# octanis_eps_v1.net
KiCad netlist of a schematic drawn in EAGLE
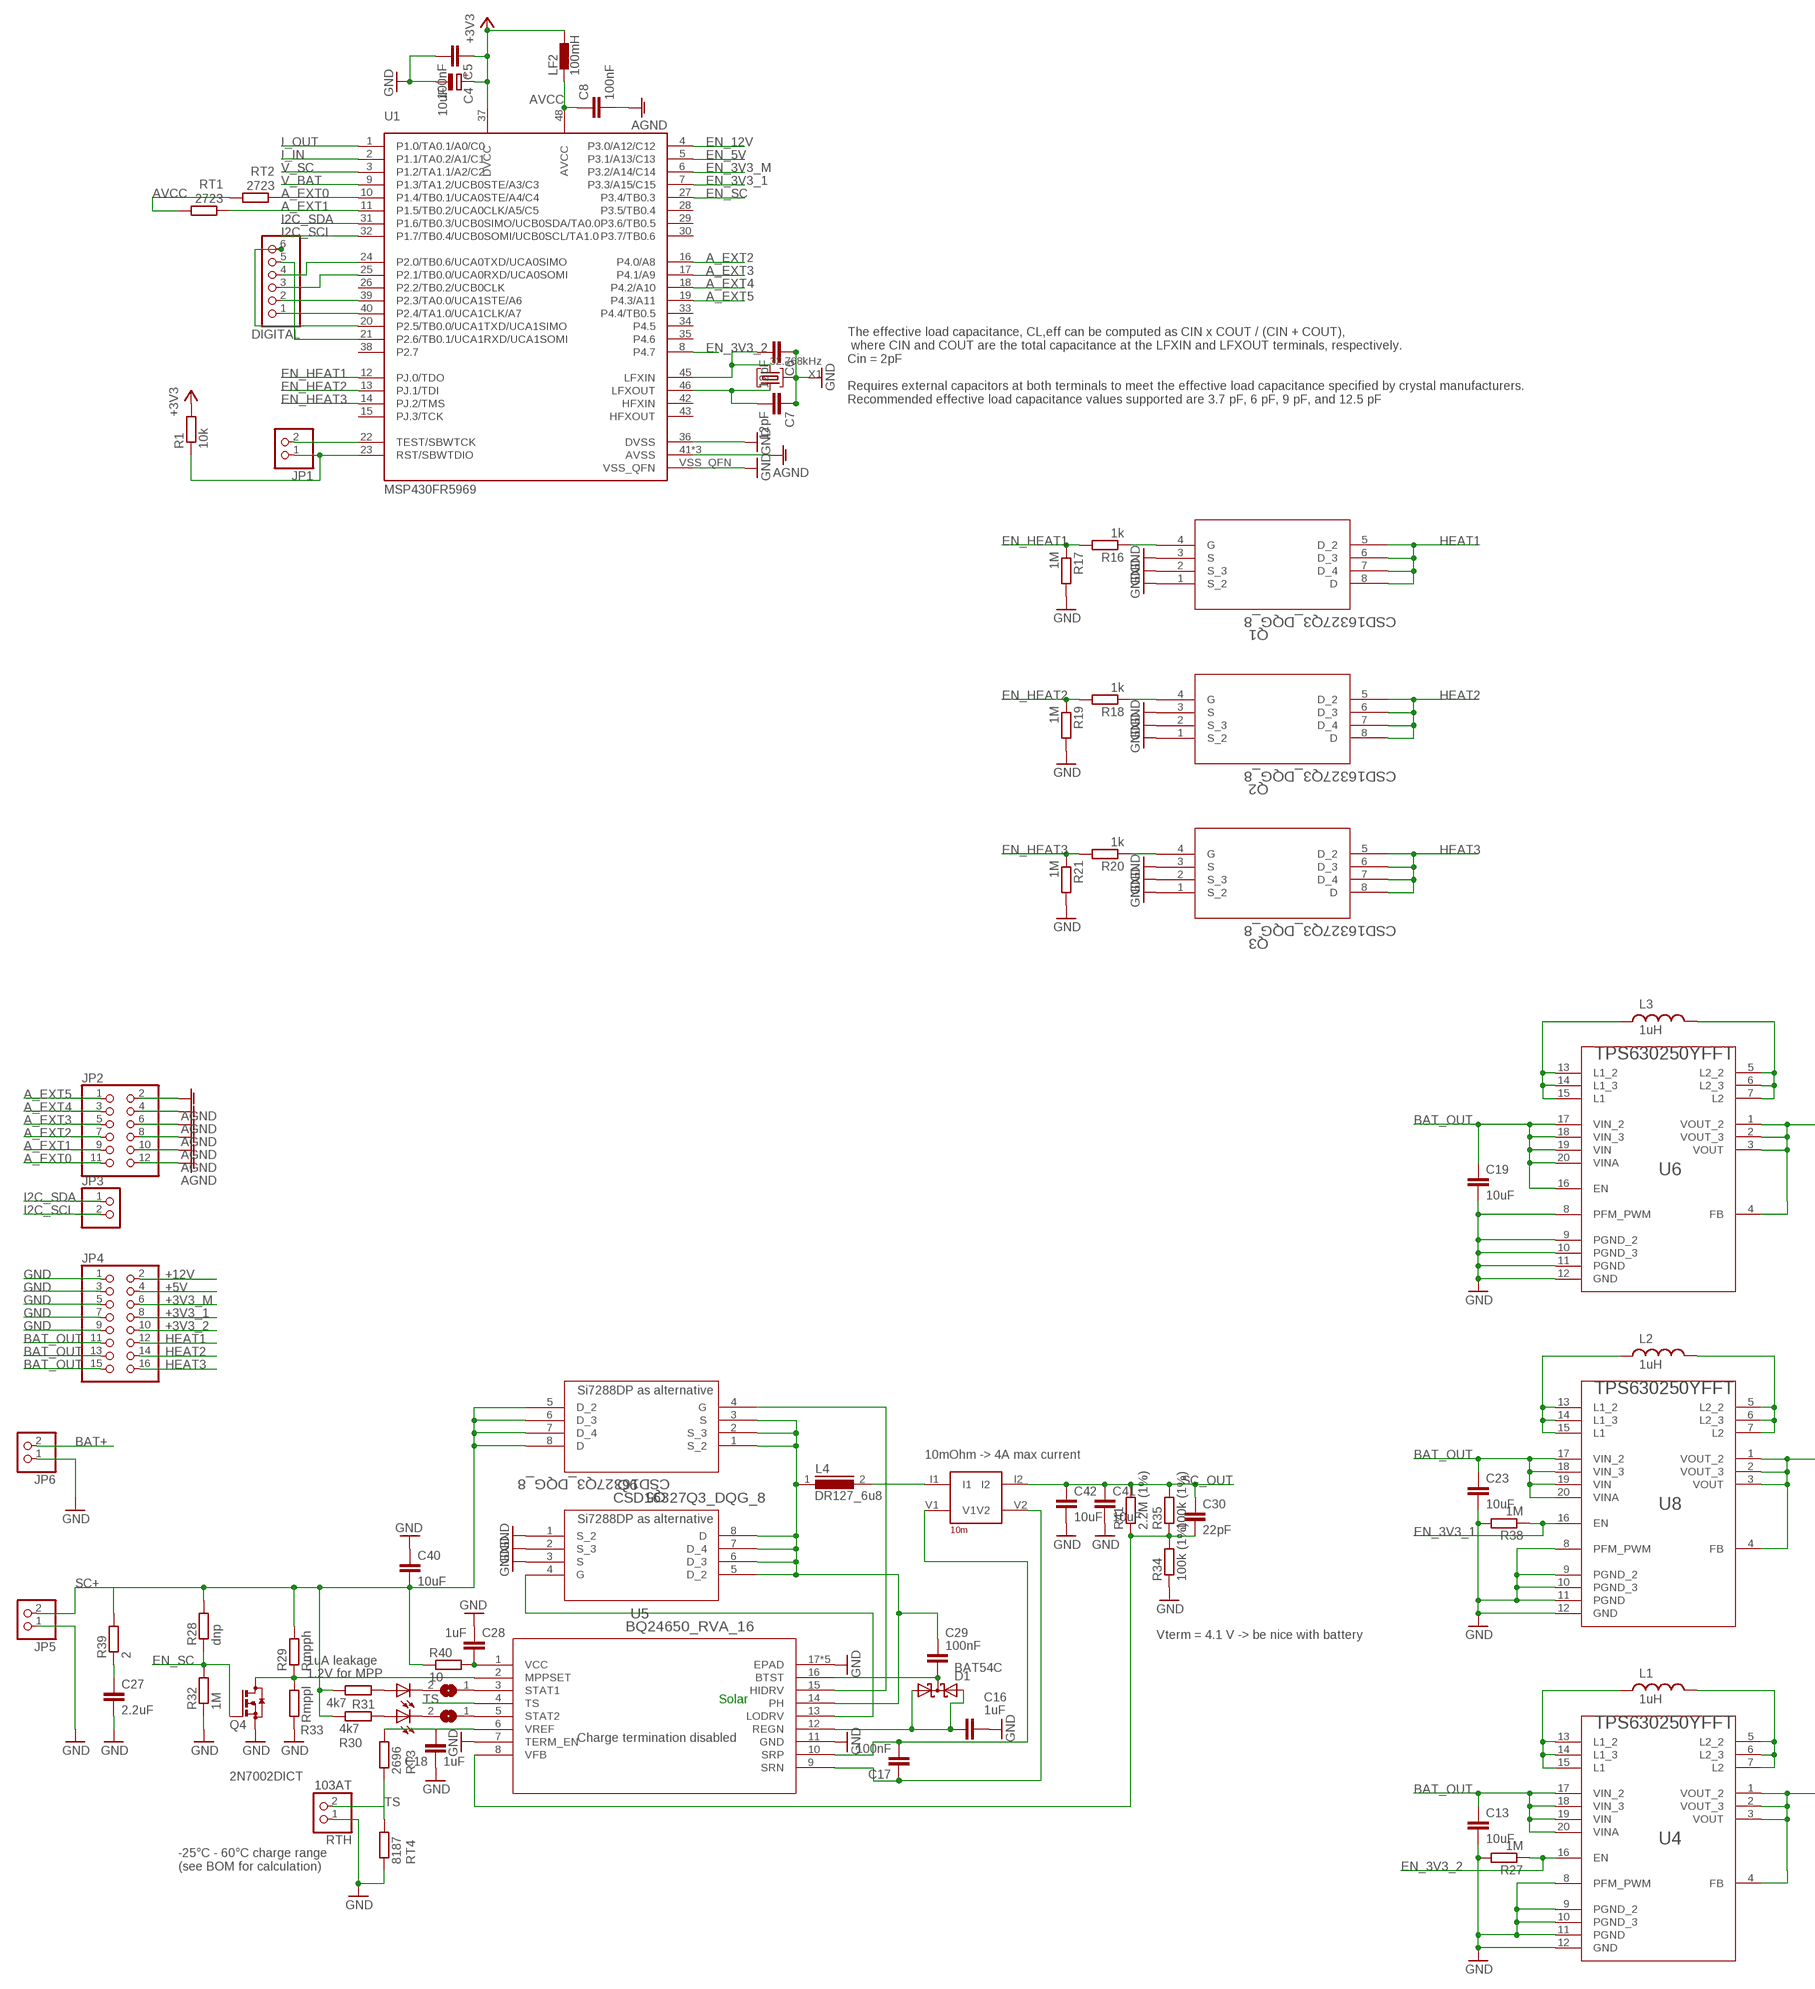
[diagram p0: schematic, sheet 1, part 1 of 2]
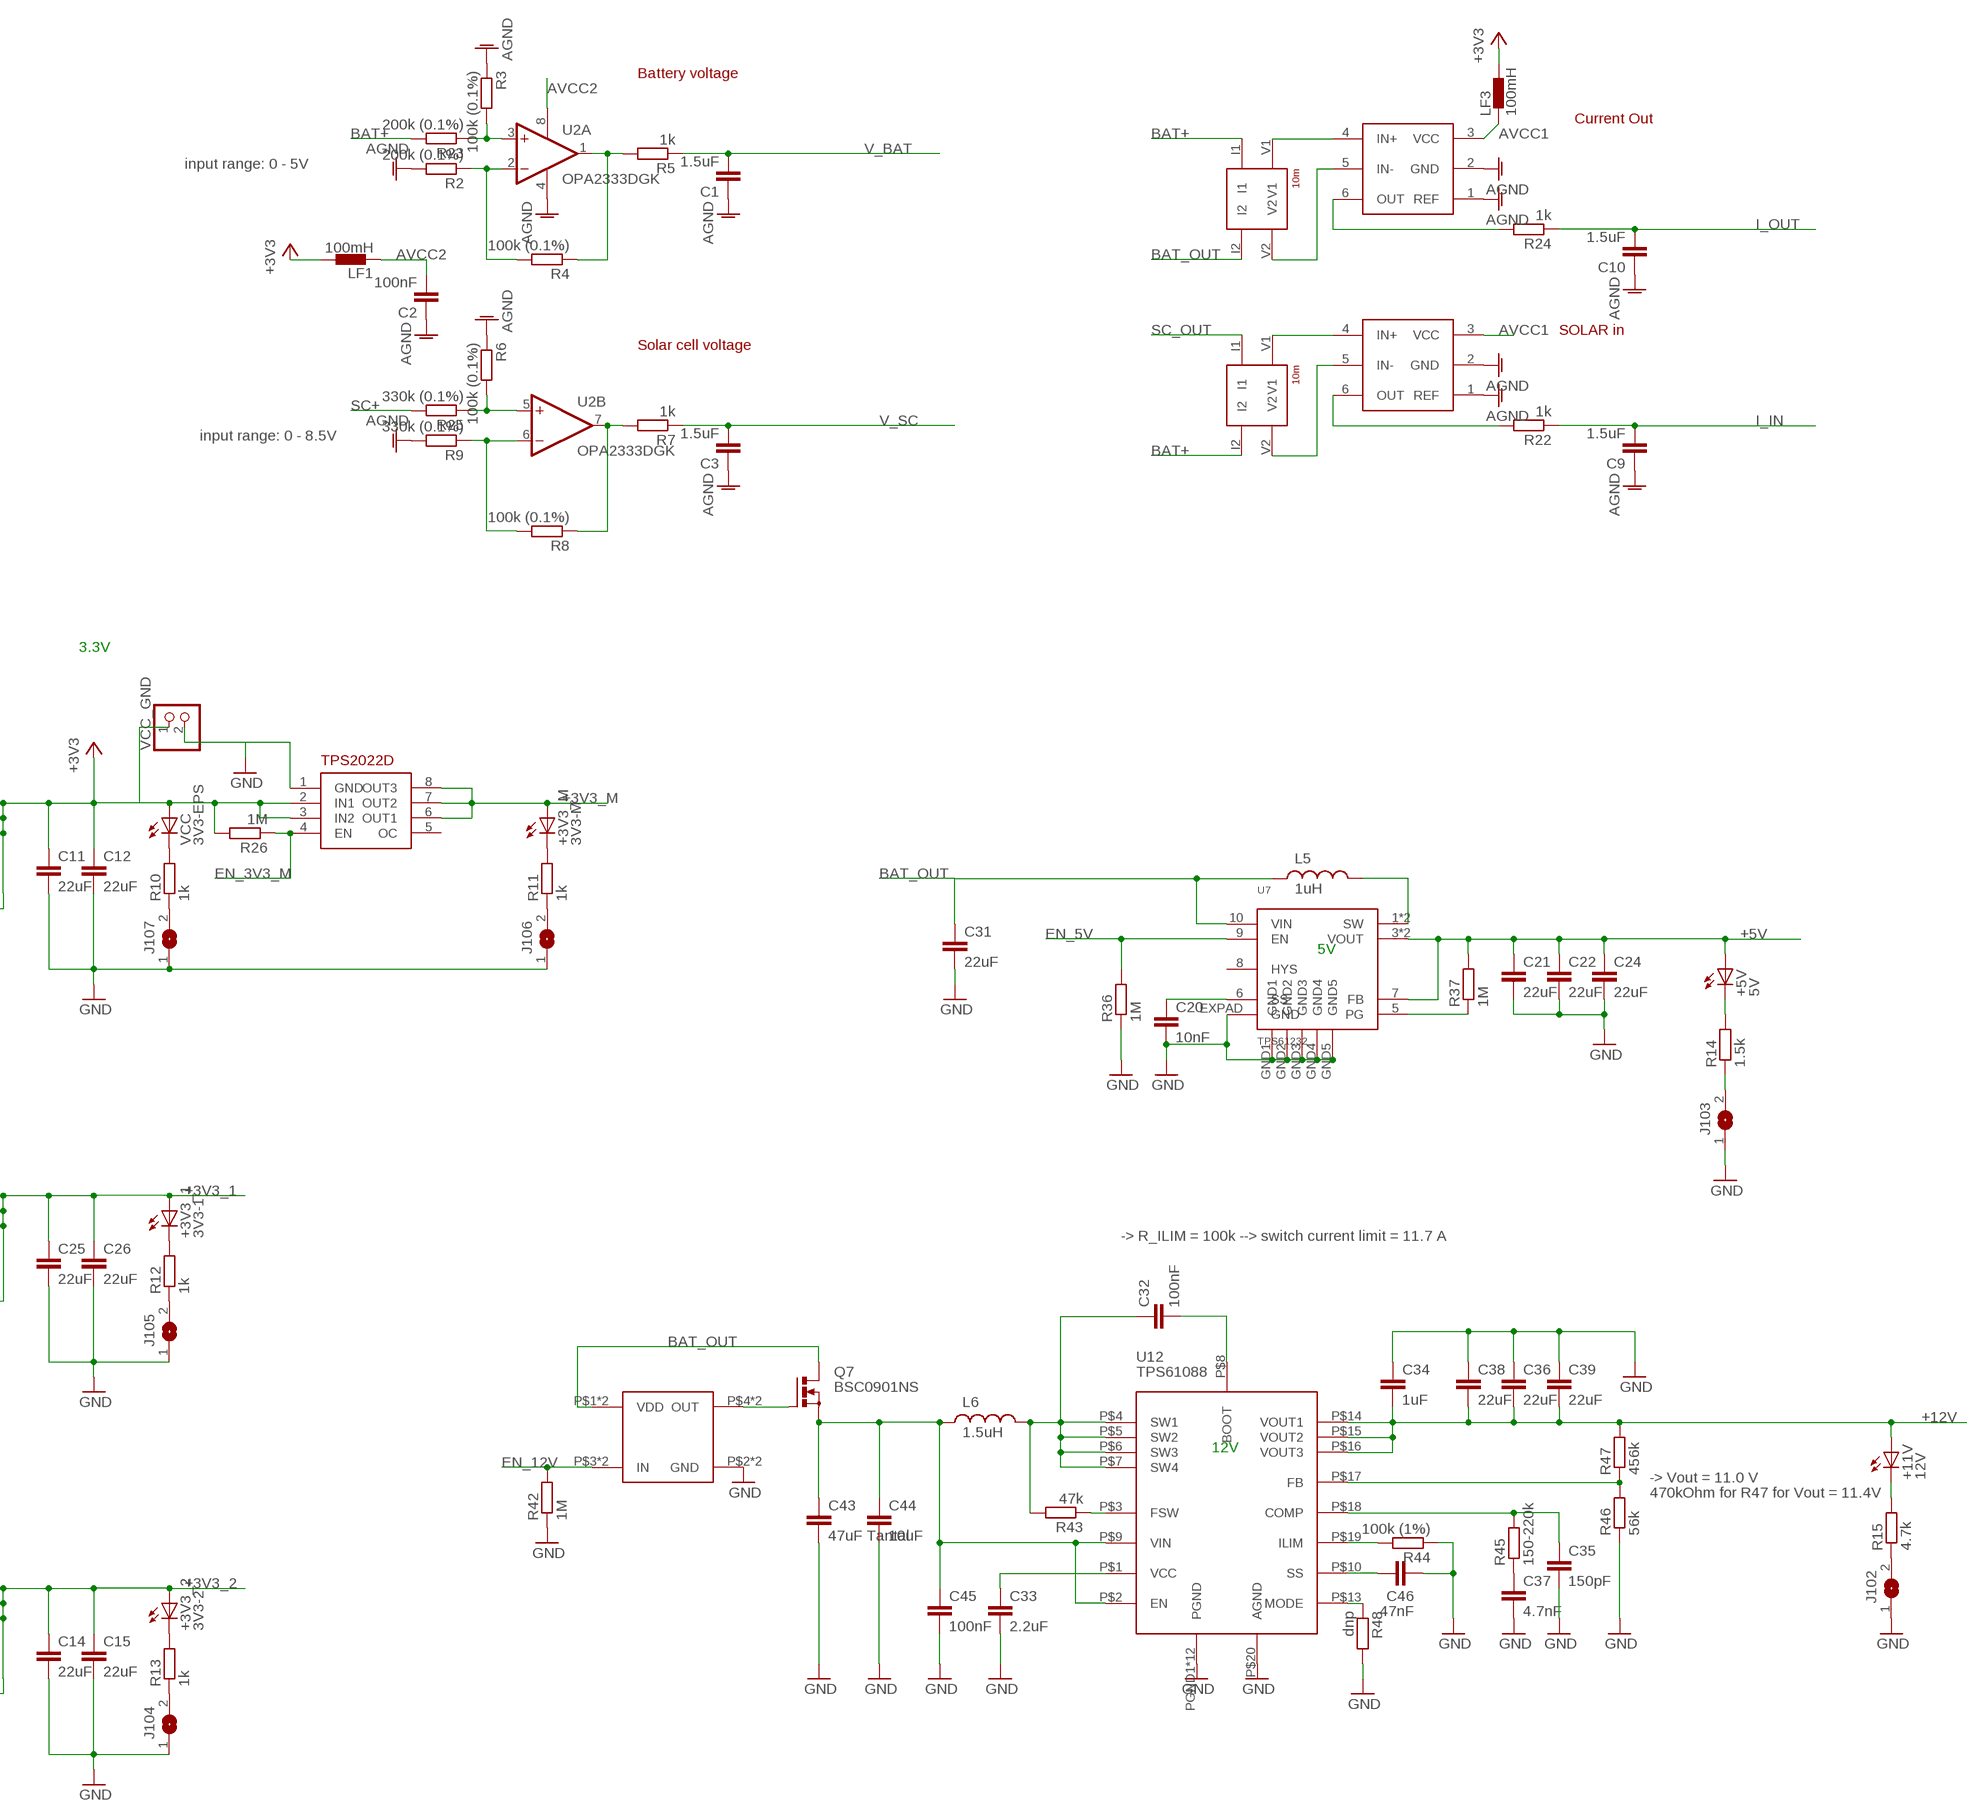
[diagram p1: schematic, sheet 1, part 2 of 2]

(export (version "E")
  (design (tool "Eeschema 10.0.6"))
  (components
    (comp (ref "+3V3_1")
      (value "3V3-1")
      (footprint "eagle-import:CHIPLED_0603")
      (libsource (lib "eagle-import") (part "LEDCHIPLED_0603"))
    )
    (comp (ref "+3V3_2")
      (value "3V3-2")
      (footprint "eagle-import:CHIPLED_0603")
      (libsource (lib "eagle-import") (part "LEDCHIPLED_0603"))
    )
    (comp (ref "+3V3_M")
      (value "3V3-M")
      (footprint "eagle-import:CHIPLED_0603")
      (libsource (lib "eagle-import") (part "LEDCHIPLED_0603"))
    )
    (comp (ref "+5V")
      (value "5V")
      (footprint "eagle-import:CHIPLED_0603")
      (libsource (lib "eagle-import") (part "LEDCHIPLED_0603"))
    )
    (comp (ref "+11V")
      (value "12V")
      (footprint "eagle-import:CHIPLED_0603")
      (libsource (lib "eagle-import") (part "LEDCHIPLED_0603"))
    )
    (comp (ref "C1")
      (value "1.5uF")
      (footprint "eagle-import:C0603")
      (libsource (lib "eagle-import") (part "C-EUC0603"))
    )
    (comp (ref "C2")
      (value "100nF")
      (footprint "eagle-import:C0603")
      (libsource (lib "eagle-import") (part "C-EUC0603"))
    )
    (comp (ref "C3")
      (value "1.5uF")
      (footprint "eagle-import:C0603")
      (libsource (lib "eagle-import") (part "C-EUC0603"))
    )
    (comp (ref "C4")
      (value "10uF")
      (footprint "eagle-import:A_3216-18R")
      (libsource (lib "eagle-import") (part "CPOL-EUA/3216-18R"))
    )
    (comp (ref "C5")
      (value "100nF")
      (footprint "eagle-import:C0603")
      (libsource (lib "eagle-import") (part "C-EUC0603"))
    )
    (comp (ref "C6")
      (value "12pF")
      (footprint "eagle-import:C0603")
      (libsource (lib "eagle-import") (part "C-EUC0603"))
    )
    (comp (ref "C7")
      (value "12pF")
      (footprint "eagle-import:C0603")
      (libsource (lib "eagle-import") (part "C-EUC0603"))
    )
    (comp (ref "C8")
      (value "100nF")
      (footprint "eagle-import:C0603")
      (libsource (lib "eagle-import") (part "C-EUC0603"))
    )
    (comp (ref "C9")
      (value "1.5uF")
      (footprint "eagle-import:C0603")
      (libsource (lib "eagle-import") (part "C-EUC0603"))
    )
    (comp (ref "C10")
      (value "1.5uF")
      (footprint "eagle-import:C0603")
      (libsource (lib "eagle-import") (part "C-EUC0603"))
    )
    (comp (ref "C11")
      (value "22uF")
      (footprint "eagle-import:C0805")
      (libsource (lib "eagle-import") (part "resistor_C-EUC0805"))
    )
    (comp (ref "C12")
      (value "22uF")
      (footprint "eagle-import:C0805")
      (libsource (lib "eagle-import") (part "resistor_C-EUC0805"))
    )
    (comp (ref "C13")
      (value "10uF")
      (footprint "eagle-import:C0805")
      (libsource (lib "eagle-import") (part "resistor_C-EUC0805"))
    )
    (comp (ref "C14")
      (value "22uF")
      (footprint "eagle-import:C0805")
      (libsource (lib "eagle-import") (part "resistor_C-EUC0805"))
    )
    (comp (ref "C15")
      (value "22uF")
      (footprint "eagle-import:C0805")
      (libsource (lib "eagle-import") (part "resistor_C-EUC0805"))
    )
    (comp (ref "C16")
      (value "1uF")
      (footprint "eagle-import:C0603")
      (libsource (lib "eagle-import") (part "C-EUC0603"))
    )
    (comp (ref "C17")
      (value "100nF")
      (footprint "eagle-import:C0603")
      (libsource (lib "eagle-import") (part "C-EUC0603"))
    )
    (comp (ref "C18")
      (value "1uF")
      (footprint "eagle-import:C0603")
      (libsource (lib "eagle-import") (part "C-EUC0603"))
    )
    (comp (ref "C19")
      (value "10uF")
      (footprint "eagle-import:C0805")
      (libsource (lib "eagle-import") (part "resistor_C-EUC0805"))
    )
    (comp (ref "C20")
      (value "10nF")
      (footprint "eagle-import:C0603")
      (libsource (lib "eagle-import") (part "C-EUC0603"))
    )
    (comp (ref "C21")
      (value "22uF")
      (footprint "eagle-import:C0805")
      (libsource (lib "eagle-import") (part "resistor_C-EUC0805"))
    )
    (comp (ref "C22")
      (value "22uF")
      (footprint "eagle-import:C0805")
      (libsource (lib "eagle-import") (part "resistor_C-EUC0805"))
    )
    (comp (ref "C23")
      (value "10uF")
      (footprint "eagle-import:C0805")
      (libsource (lib "eagle-import") (part "resistor_C-EUC0805"))
    )
    (comp (ref "C24")
      (value "22uF")
      (footprint "eagle-import:C0805")
      (libsource (lib "eagle-import") (part "resistor_C-EUC0805"))
    )
    (comp (ref "C25")
      (value "22uF")
      (footprint "eagle-import:C0805")
      (libsource (lib "eagle-import") (part "resistor_C-EUC0805"))
    )
    (comp (ref "C26")
      (value "22uF")
      (footprint "eagle-import:C0805")
      (libsource (lib "eagle-import") (part "resistor_C-EUC0805"))
    )
    (comp (ref "C27")
      (value "2.2uF")
      (footprint "eagle-import:C0603")
      (libsource (lib "eagle-import") (part "C-EUC0603"))
    )
    (comp (ref "C28")
      (value "1uF")
      (footprint "eagle-import:C0603")
      (libsource (lib "eagle-import") (part "C-EUC0603"))
    )
    (comp (ref "C29")
      (value "100nF")
      (footprint "eagle-import:C0603")
      (libsource (lib "eagle-import") (part "C-EUC0603"))
    )
    (comp (ref "C30")
      (value "22pF")
      (footprint "eagle-import:C0603")
      (libsource (lib "eagle-import") (part "C-EUC0603"))
    )
    (comp (ref "C31")
      (value "22uF")
      (footprint "eagle-import:C0603")
      (libsource (lib "eagle-import") (part "C-EUC0603"))
    )
    (comp (ref "C32")
      (value "100nF")
      (footprint "eagle-import:C0603")
      (libsource (lib "eagle-import") (part "C-EUC0603"))
    )
    (comp (ref "C33")
      (value "2.2uF")
      (footprint "eagle-import:C0603")
      (libsource (lib "eagle-import") (part "C-EUC0603"))
    )
    (comp (ref "C34")
      (value "1uF")
      (footprint "eagle-import:C0603")
      (libsource (lib "eagle-import") (part "C-EUC0603"))
    )
    (comp (ref "C35")
      (value "150pF")
      (footprint "eagle-import:C0603")
      (libsource (lib "eagle-import") (part "C-EUC0603"))
    )
    (comp (ref "C36")
      (value "22uF")
      (footprint "eagle-import:C0805")
      (libsource (lib "eagle-import") (part "resistor_C-EUC0805"))
    )
    (comp (ref "C37")
      (value "4.7nF")
      (footprint "eagle-import:C0603")
      (libsource (lib "eagle-import") (part "C-EUC0603"))
    )
    (comp (ref "C38")
      (value "22uF")
      (footprint "eagle-import:C0805")
      (libsource (lib "eagle-import") (part "resistor_C-EUC0805"))
    )
    (comp (ref "C39")
      (value "22uF")
      (footprint "eagle-import:C0805")
      (libsource (lib "eagle-import") (part "resistor_C-EUC0805"))
    )
    (comp (ref "C40")
      (value "10uF")
      (footprint "eagle-import:C0805")
      (libsource (lib "eagle-import") (part "resistor_C-EUC0805"))
    )
    (comp (ref "C41")
      (value "10uF")
      (footprint "eagle-import:C0805")
      (libsource (lib "eagle-import") (part "resistor_C-EUC0805"))
    )
    (comp (ref "C42")
      (value "10uF")
      (footprint "eagle-import:C0805")
      (libsource (lib "eagle-import") (part "resistor_C-EUC0805"))
    )
    (comp (ref "C43")
      (value "47uF Tantal")
      (footprint "eagle-import:C1210")
      (libsource (lib "eagle-import") (part "C-EUC1210"))
    )
    (comp (ref "C44")
      (value "10uF")
      (footprint "eagle-import:C0805")
      (libsource (lib "eagle-import") (part "resistor_C-EUC0805"))
    )
    (comp (ref "C45")
      (value "100nF")
      (footprint "eagle-import:C0603")
      (libsource (lib "eagle-import") (part "C-EUC0603"))
    )
    (comp (ref "C46")
      (value "47nF")
      (footprint "eagle-import:C0603")
      (libsource (lib "eagle-import") (part "C-EUC0603"))
    )
    (comp (ref "D1")
      (value "BAT54C")
      (footprint "eagle-import:SOT23")
      (libsource (lib "eagle-import") (part "BAT54C"))
    )
    (comp (ref "DIGITAL")
      (value "PINHD-1X6B")
      (footprint "eagle-import:1X06-BIG")
      (libsource (lib "eagle-import") (part "PINHD-1X6B"))
    )
    (comp (ref "J100")
      (value "SJ")
      (footprint "eagle-import:SJ")
      (libsource (lib "eagle-import") (part "SJ"))
    )
    (comp (ref "J101")
      (value "SJ")
      (footprint "eagle-import:SJ")
      (libsource (lib "eagle-import") (part "SJ"))
    )
    (comp (ref "J102")
      (value "SJ")
      (footprint "eagle-import:SJ")
      (libsource (lib "eagle-import") (part "SJ"))
    )
    (comp (ref "J103")
      (value "SJ")
      (footprint "eagle-import:SJ")
      (libsource (lib "eagle-import") (part "SJ"))
    )
    (comp (ref "J104")
      (value "SJ")
      (footprint "eagle-import:SJ")
      (libsource (lib "eagle-import") (part "SJ"))
    )
    (comp (ref "J105")
      (value "SJ")
      (footprint "eagle-import:SJ")
      (libsource (lib "eagle-import") (part "SJ"))
    )
    (comp (ref "J106")
      (value "SJ")
      (footprint "eagle-import:SJ")
      (libsource (lib "eagle-import") (part "SJ"))
    )
    (comp (ref "J107")
      (value "SJ")
      (footprint "eagle-import:SJ")
      (libsource (lib "eagle-import") (part "SJ"))
    )
    (comp (ref "JP1")
      (value "PINHD-1X2")
      (footprint "eagle-import:1X02")
      (libsource (lib "eagle-import") (part "PINHD-1X2"))
    )
    (comp (ref "JP2")
      (value "PINHD-2X6")
      (footprint "eagle-import:2X06")
      (libsource (lib "eagle-import") (part "PINHD-2X6"))
    )
    (comp (ref "JP3")
      (value "PINHD-1X2")
      (footprint "eagle-import:1X02")
      (libsource (lib "eagle-import") (part "PINHD-1X2"))
    )
    (comp (ref "JP4")
      (value "PINHD-2X8")
      (footprint "eagle-import:2X08")
      (libsource (lib "eagle-import") (part "PINHD-2X8"))
    )
    (comp (ref "JP5")
      (value "PINHD-1X2")
      (footprint "eagle-import:1X02")
      (libsource (lib "eagle-import") (part "PINHD-1X2"))
    )
    (comp (ref "JP6")
      (value "PINHD-1X2")
      (footprint "eagle-import:1X02")
      (libsource (lib "eagle-import") (part "PINHD-1X2"))
    )
    (comp (ref "L1")
      (value "1uH")
      (footprint "eagle-import:XFL4020")
      (libsource (lib "eagle-import") (part "XFL4020"))
    )
    (comp (ref "L2")
      (value "1uH")
      (footprint "eagle-import:XFL4020")
      (libsource (lib "eagle-import") (part "XFL4020"))
    )
    (comp (ref "L3")
      (value "1uH")
      (footprint "eagle-import:XFL4020")
      (libsource (lib "eagle-import") (part "XFL4020"))
    )
    (comp (ref "L4")
      (value "DR127_6u8")
      (footprint "eagle-import:DR127")
      (libsource (lib "eagle-import") (part "DR127"))
    )
    (comp (ref "L5")
      (value "1uH")
      (footprint "eagle-import:XFL4020")
      (libsource (lib "eagle-import") (part "XFL4020"))
    )
    (comp (ref "L6")
      (value "1.5uH")
      (footprint "eagle-import:XFL4020")
      (libsource (lib "eagle-import") (part "XFL4020"))
    )
    (comp (ref "LF1")
      (value "100mH")
      (footprint "eagle-import:0402")
      (libsource (lib "eagle-import") (part "BLM15HD601SN1"))
    )
    (comp (ref "LF2")
      (value "100mH")
      (footprint "eagle-import:0402")
      (libsource (lib "eagle-import") (part "BLM15HD601SN1"))
    )
    (comp (ref "LF3")
      (value "100mH")
      (footprint "eagle-import:0402")
      (libsource (lib "eagle-import") (part "BLM15HD601SN1"))
    )
    (comp (ref "Q1")
      (value "CSD16327Q3_DQG_8")
      (footprint "eagle-import:DQG8")
      (fields
        (field (name "GENERIC_PART_NUMBER") "CSD16327Q3")
        (field (name "MANUFACTURER") "Texas Instruments")
      )
      (libsource (lib "eagle-import") (part "CSD16327Q3_DQG_8"))
    )
    (comp (ref "Q2")
      (value "CSD16327Q3_DQG_8")
      (footprint "eagle-import:DQG8")
      (fields
        (field (name "GENERIC_PART_NUMBER") "CSD16327Q3")
        (field (name "MANUFACTURER") "Texas Instruments")
      )
      (libsource (lib "eagle-import") (part "CSD16327Q3_DQG_8"))
    )
    (comp (ref "Q3")
      (value "CSD16327Q3_DQG_8")
      (footprint "eagle-import:DQG8")
      (fields
        (field (name "GENERIC_PART_NUMBER") "CSD16327Q3")
        (field (name "MANUFACTURER") "Texas Instruments")
      )
      (libsource (lib "eagle-import") (part "CSD16327Q3_DQG_8"))
    )
    (comp (ref "Q4")
      (value "BSS123")
      (footprint "eagle-import:SOT23")
      (libsource (lib "eagle-import") (part "BSS123"))
    )
    (comp (ref "Q5")
      (value "CSD16327Q3_DQG_8")
      (footprint "eagle-import:DQG8")
      (fields
        (field (name "GENERIC_PART_NUMBER") "CSD16327Q3")
        (field (name "MANUFACTURER") "Texas Instruments")
      )
      (libsource (lib "eagle-import") (part "CSD16327Q3_DQG_8"))
    )
    (comp (ref "Q6")
      (value "CSD16327Q3_DQG_8")
      (footprint "eagle-import:DQG8")
      (fields
        (field (name "GENERIC_PART_NUMBER") "CSD16327Q3")
        (field (name "MANUFACTURER") "Texas Instruments")
      )
      (libsource (lib "eagle-import") (part "CSD16327Q3_DQG_8"))
    )
    (comp (ref "Q7")
      (value "BSC0901NS")
      (footprint "eagle-import:PG-TDSON-8")
      (libsource (lib "eagle-import") (part "BSC340N08NS3G"))
    )
    (comp (ref "R1")
      (value "10k")
      (footprint "eagle-import:R0603")
      (libsource (lib "eagle-import") (part "R-EU_R0603"))
    )
    (comp (ref "R2")
      (value "200k (0.1%)")
      (footprint "eagle-import:R0603")
      (libsource (lib "eagle-import") (part "R-EU_R0603"))
    )
    (comp (ref "R3")
      (value "100k (0.1%)")
      (footprint "eagle-import:R0603")
      (libsource (lib "eagle-import") (part "R-EU_R0603"))
    )
    (comp (ref "R4")
      (value "100k (0.1%)")
      (footprint "eagle-import:R0603")
      (libsource (lib "eagle-import") (part "R-EU_R0603"))
    )
    (comp (ref "R5")
      (value "1k")
      (footprint "eagle-import:R0603")
      (libsource (lib "eagle-import") (part "R-EU_R0603"))
    )
    (comp (ref "R6")
      (value "100k (0.1%)")
      (footprint "eagle-import:R0603")
      (libsource (lib "eagle-import") (part "R-EU_R0603"))
    )
    (comp (ref "R7")
      (value "1k")
      (footprint "eagle-import:R0603")
      (libsource (lib "eagle-import") (part "R-EU_R0603"))
    )
    (comp (ref "R8")
      (value "100k (0.1%)")
      (footprint "eagle-import:R0603")
      (libsource (lib "eagle-import") (part "R-EU_R0603"))
    )
    (comp (ref "R9")
      (value "330k (0.1%)")
      (footprint "eagle-import:R0603")
      (libsource (lib "eagle-import") (part "R-EU_R0603"))
    )
    (comp (ref "R10")
      (value "1k")
      (footprint "eagle-import:R0603")
      (libsource (lib "eagle-import") (part "R-EU_R0603"))
    )
    (comp (ref "R11")
      (value "1k")
      (footprint "eagle-import:R0603")
      (libsource (lib "eagle-import") (part "R-EU_R0603"))
    )
    (comp (ref "R12")
      (value "1k")
      (footprint "eagle-import:R0603")
      (libsource (lib "eagle-import") (part "R-EU_R0603"))
    )
    (comp (ref "R13")
      (value "1k")
      (footprint "eagle-import:R0603")
      (libsource (lib "eagle-import") (part "R-EU_R0603"))
    )
    (comp (ref "R14")
      (value "1.5k")
      (footprint "eagle-import:R0603")
      (libsource (lib "eagle-import") (part "R-EU_R0603"))
    )
    (comp (ref "R15")
      (value "4.7k")
      (footprint "eagle-import:R0603")
      (libsource (lib "eagle-import") (part "R-EU_R0603"))
    )
    (comp (ref "R16")
      (value "1k")
      (footprint "eagle-import:R0603")
      (libsource (lib "eagle-import") (part "R-EU_R0603"))
    )
    (comp (ref "R17")
      (value "1M")
      (footprint "eagle-import:R0603")
      (libsource (lib "eagle-import") (part "R-EU_R0603"))
    )
    (comp (ref "R18")
      (value "1k")
      (footprint "eagle-import:R0603")
      (libsource (lib "eagle-import") (part "R-EU_R0603"))
    )
    (comp (ref "R19")
      (value "1M")
      (footprint "eagle-import:R0603")
      (libsource (lib "eagle-import") (part "R-EU_R0603"))
    )
    (comp (ref "R20")
      (value "1k")
      (footprint "eagle-import:R0603")
      (libsource (lib "eagle-import") (part "R-EU_R0603"))
    )
    (comp (ref "R21")
      (value "1M")
      (footprint "eagle-import:R0603")
      (libsource (lib "eagle-import") (part "R-EU_R0603"))
    )
    (comp (ref "R22")
      (value "1k")
      (footprint "eagle-import:R0603")
      (libsource (lib "eagle-import") (part "R-EU_R0603"))
    )
    (comp (ref "R23")
      (value "200k (0.1%)")
      (footprint "eagle-import:R0603")
      (libsource (lib "eagle-import") (part "R-EU_R0603"))
    )
    (comp (ref "R24")
      (value "1k")
      (footprint "eagle-import:R0603")
      (libsource (lib "eagle-import") (part "R-EU_R0603"))
    )
    (comp (ref "R25")
      (value "330k (0.1%)")
      (footprint "eagle-import:R0603")
      (libsource (lib "eagle-import") (part "R-EU_R0603"))
    )
    (comp (ref "R26")
      (value "1M")
      (footprint "eagle-import:R0603")
      (libsource (lib "eagle-import") (part "resistor_R-EU_R0603"))
    )
    (comp (ref "R27")
      (value "1M")
      (footprint "eagle-import:R0603")
      (libsource (lib "eagle-import") (part "resistor_R-EU_R0603"))
    )
    (comp (ref "R28")
      (value "dnp")
      (footprint "eagle-import:R0603")
      (libsource (lib "eagle-import") (part "R-EU_R0603"))
    )
    (comp (ref "R29")
      (value "Rmpph")
      (footprint "eagle-import:R0603")
      (libsource (lib "eagle-import") (part "R-EU_R0603"))
    )
    (comp (ref "R30")
      (value "4k7")
      (footprint "eagle-import:R0603")
      (libsource (lib "eagle-import") (part "R-EU_R0603"))
    )
    (comp (ref "R31")
      (value "4k7")
      (footprint "eagle-import:R0603")
      (libsource (lib "eagle-import") (part "R-EU_R0603"))
    )
    (comp (ref "R32")
      (value "1M")
      (footprint "eagle-import:R0603")
      (libsource (lib "eagle-import") (part "R-EU_R0603"))
    )
    (comp (ref "R33")
      (value "Rmppl")
      (footprint "eagle-import:R0603")
      (libsource (lib "eagle-import") (part "R-EU_R0603"))
    )
    (comp (ref "R34")
      (value "100k (1%)")
      (footprint "eagle-import:R0603")
      (libsource (lib "eagle-import") (part "R-EU_R0603"))
    )
    (comp (ref "R35")
      (value "100k (1%)")
      (footprint "eagle-import:R0603")
      (libsource (lib "eagle-import") (part "R-EU_R0603"))
    )
    (comp (ref "R36")
      (value "1M")
      (footprint "eagle-import:R0603")
      (libsource (lib "eagle-import") (part "R-EU_R0603"))
    )
    (comp (ref "R37")
      (value "1M")
      (footprint "eagle-import:R0603")
      (libsource (lib "eagle-import") (part "R-EU_R0603"))
    )
    (comp (ref "R38")
      (value "1M")
      (footprint "eagle-import:R0603")
      (libsource (lib "eagle-import") (part "resistor_R-EU_R0603"))
    )
    (comp (ref "R39")
      (value "2")
      (footprint "eagle-import:R2010")
      (libsource (lib "eagle-import") (part "R-EU_R2010"))
    )
    (comp (ref "R40")
      (value "10")
      (footprint "eagle-import:R1206")
      (libsource (lib "eagle-import") (part "R-EU_R1206"))
    )
    (comp (ref "R41")
      (value "2.2M (1%)")
      (footprint "eagle-import:R0603")
      (libsource (lib "eagle-import") (part "R-EU_R0603"))
    )
    (comp (ref "R42")
      (value "1M")
      (footprint "eagle-import:R0603")
      (libsource (lib "eagle-import") (part "R-EU_R0603"))
    )
    (comp (ref "R43")
      (value "47k")
      (footprint "eagle-import:R0603")
      (libsource (lib "eagle-import") (part "resistor_R-EU_R0603"))
    )
    (comp (ref "R44")
      (value "100k (1%)")
      (footprint "eagle-import:R0603")
      (libsource (lib "eagle-import") (part "resistor_R-EU_R0603"))
    )
    (comp (ref "R45")
      (value "150-220k")
      (footprint "eagle-import:R0603")
      (libsource (lib "eagle-import") (part "resistor_R-EU_R0603"))
    )
    (comp (ref "R46")
      (value "56k")
      (footprint "eagle-import:R0603")
      (libsource (lib "eagle-import") (part "resistor_R-EU_R0603"))
    )
    (comp (ref "R47")
      (value "456k")
      (footprint "eagle-import:R0603")
      (libsource (lib "eagle-import") (part "resistor_R-EU_R0603"))
    )
    (comp (ref "R48")
      (value "dnp")
      (footprint "eagle-import:R0603")
      (libsource (lib "eagle-import") (part "resistor_R-EU_R0603"))
    )
    (comp (ref "RS1")
      (value "10m")
      (footprint "eagle-import:4PADS_RESISTOR")
      (libsource (lib "eagle-import") (part "CURRENT_RESISTOR"))
    )
    (comp (ref "RS2")
      (value "10m")
      (footprint "eagle-import:4PADS_RESISTOR")
      (libsource (lib "eagle-import") (part "CURRENT_RESISTOR"))
    )
    (comp (ref "RS3")
      (value "10m")
      (footprint "eagle-import:4PADS_RESISTOR")
      (libsource (lib "eagle-import") (part "CURRENT_RESISTOR"))
    )
    (comp (ref "RT1")
      (value "2723")
      (footprint "eagle-import:R0603")
      (libsource (lib "eagle-import") (part "R-EU_R0603"))
    )
    (comp (ref "RT2")
      (value "2723")
      (footprint "eagle-import:R0603")
      (libsource (lib "eagle-import") (part "R-EU_R0603"))
    )
    (comp (ref "RT3")
      (value "2696")
      (footprint "eagle-import:R0603")
      (libsource (lib "eagle-import") (part "R-EU_R0603"))
    )
    (comp (ref "RT4")
      (value "8187")
      (footprint "eagle-import:R0603")
      (libsource (lib "eagle-import") (part "R-EU_R0603"))
    )
    (comp (ref "RTH")
      (value "103AT")
      (footprint "eagle-import:1X02")
      (libsource (lib "eagle-import") (part "PINHD-1X2"))
    )
    (comp (ref "STAT1")
      (value "5V-ok")
      (footprint "eagle-import:CHIPLED_0603")
      (libsource (lib "eagle-import") (part "LEDCHIPLED_0603"))
    )
    (comp (ref "STAT2")
      (value "5V-ok")
      (footprint "eagle-import:CHIPLED_0603")
      (libsource (lib "eagle-import") (part "LEDCHIPLED_0603"))
    )
    (comp (ref "U1")
      (value "MSP430FR5969")
      (footprint "eagle-import:S-PVQFN-N48")
      (libsource (lib "eagle-import") (part "MSP430FR5969"))
    )
    (comp (ref "U2")
      (value "OPA2333DGK")
      (footprint "eagle-import:MSOP08")
      (libsource (lib "eagle-import") (part "OPA2333DGK"))
    )
    (comp (ref "U3")
      (value "TPS2022D")
      (footprint "eagle-import:SO8")
      (libsource (lib "eagle-import") (part "TPS2022D"))
    )
    (comp (ref "U4")
      (value "TPS630250YFFT")
      (footprint "eagle-import:YFF0020AEBA")
      (fields
        (field (name "MANUFACTURER") "Texas Instruments")
        (field (name "PARTNUMBER") "TPS630250YFF")
        (field (name "APPROVEDBY") "Not shown in title block")
        (field (name "AUTHOR") "Not shown in title block")
        (field (name "CHECKEDBY") "Not shown in title block")
        (field (name "ENGINEER") "Not shown in title block")
        (field (name "MODIFIEDDATE") "Not shown in title block")
        (field (name "PUBLISHER") "Texas Instruments")
        (field (name "SYMBOLCREATOR") "a0411947")
      )
      (libsource (lib "eagle-import") (part "TPS630250YFFT"))
    )
    (comp (ref "U5")
      (value "BQ24650_RVA_16")
      (footprint "eagle-import:RVA16_2P14X2P14")
      (fields
        (field (name "GENERIC_PART_NUMBER") "BQ24650")
        (field (name "MANUFACTURER") "Texas Instruments")
      )
      (libsource (lib "eagle-import") (part "BQ24650_RVA_16"))
    )
    (comp (ref "U6")
      (value "TPS630250YFFT")
      (footprint "eagle-import:YFF0020AEBA")
      (fields
        (field (name "MANUFACTURER") "Texas Instruments")
        (field (name "PARTNUMBER") "TPS630250YFF")
        (field (name "APPROVEDBY") "Not shown in title block")
        (field (name "AUTHOR") "Not shown in title block")
        (field (name "CHECKEDBY") "Not shown in title block")
        (field (name "ENGINEER") "Not shown in title block")
        (field (name "MODIFIEDDATE") "Not shown in title block")
        (field (name "PUBLISHER") "Texas Instruments")
        (field (name "SYMBOLCREATOR") "a0411947")
      )
      (libsource (lib "eagle-import") (part "TPS630250YFFT"))
    )
    (comp (ref "U7")
      (value "TPS61232")
      (footprint "eagle-import:S-PVSON-N10")
      (libsource (lib "eagle-import") (part "TPS61232"))
    )
    (comp (ref "U8")
      (value "TPS630250YFFT")
      (footprint "eagle-import:YFF0020AEBA")
      (fields
        (field (name "MANUFACTURER") "Texas Instruments")
        (field (name "PARTNUMBER") "TPS630250YFF")
        (field (name "APPROVEDBY") "Not shown in title block")
        (field (name "AUTHOR") "Not shown in title block")
        (field (name "CHECKEDBY") "Not shown in title block")
        (field (name "ENGINEER") "Not shown in title block")
        (field (name "MODIFIEDDATE") "Not shown in title block")
        (field (name "PUBLISHER") "Texas Instruments")
        (field (name "SYMBOLCREATOR") "a0411947")
      )
      (libsource (lib "eagle-import") (part "TPS630250YFFT"))
    )
    (comp (ref "U9")
      (value "INA213")
      (footprint "eagle-import:SC70-6")
      (libsource (lib "eagle-import") (part "INA213"))
    )
    (comp (ref "U10")
      (value "INA213")
      (footprint "eagle-import:SC70-6")
      (libsource (lib "eagle-import") (part "INA213"))
    )
    (comp (ref "U11")
      (value "MIC5019")
      (footprint "eagle-import:QFN-4")
      (libsource (lib "eagle-import") (part "MIC5019"))
    )
    (comp (ref "U12")
      (value "TPS61088")
      (footprint "eagle-import:R-PVQFN-N20")
      (libsource (lib "eagle-import") (part "TPS61088"))
    )
    (comp (ref "VCC")
      (value "3V3-EPS")
      (footprint "eagle-import:CHIPLED_0603")
      (libsource (lib "eagle-import") (part "LEDCHIPLED_0603"))
    )
    (comp (ref "VCC_GND")
      (value "PINHD-1X2")
      (footprint "eagle-import:1X02")
      (libsource (lib "eagle-import") (part "PINHD-1X2"))
    )
    (comp (ref "X1")
      (value "32.768kHz")
      (footprint "eagle-import:MS3V-T1R")
      (libsource (lib "eagle-import") (part "MS3V-T1R"))
    )
  )
  (nets
    (net (code "1") (name "+3V3") (class "Default")
      (node (ref "C11") (pin "1") (pinfunction "1_1") (pintype "passive"))
      (node (ref "C12") (pin "1") (pinfunction "1_1") (pintype "passive"))
      (node (ref "C4") (pin "+") (pinfunction "+_+") (pintype "passive"))
      (node (ref "C5") (pin "1") (pinfunction "1_1") (pintype "passive"))
      (node (ref "LF1") (pin "2") (pinfunction "2_2") (pintype "passive"))
      (node (ref "LF2") (pin "2") (pinfunction "2_2") (pintype "passive"))
      (node (ref "LF3") (pin "2") (pinfunction "2_2") (pintype "passive"))
      (node (ref "R1") (pin "2") (pinfunction "2_2") (pintype "passive"))
      (node (ref "R26") (pin "2") (pinfunction "2_2") (pintype "passive"))
      (node (ref "U1") (pin "37") (pinfunction "DVCC_37") (pintype "bidirectional"))
      (node (ref "U3") (pin "2") (pinfunction "IN1_2") (pintype "bidirectional"))
      (node (ref "U3") (pin "3") (pinfunction "IN2_3") (pintype "bidirectional"))
      (node (ref "U6") (pin "1") (pinfunction "VOUT_2_1") (pintype "passive"))
      (node (ref "U6") (pin "2") (pinfunction "VOUT_3_2") (pintype "power_in"))
      (node (ref "U6") (pin "3") (pinfunction "VOUT_3") (pintype "power_in"))
      (node (ref "U6") (pin "4") (pinfunction "FB_4") (pintype "input"))
      (node (ref "VCC") (pin "A") (pinfunction "A_A") (pintype "passive"))
      (node (ref "VCC_GND") (pin "1") (pinfunction "1_1") (pintype "passive"))
    )
    (net (code "2") (name "/+3V3_1") (class "Default")
      (node (ref "+3V3_1") (pin "A") (pinfunction "A_A") (pintype "passive"))
      (node (ref "C25") (pin "1") (pinfunction "1_1") (pintype "passive"))
      (node (ref "C26") (pin "1") (pinfunction "1_1") (pintype "passive"))
      (node (ref "JP4") (pin "8") (pinfunction "8_8") (pintype "passive"))
      (node (ref "U8") (pin "1") (pinfunction "VOUT_2_1") (pintype "passive"))
      (node (ref "U8") (pin "2") (pinfunction "VOUT_3_2") (pintype "power_in"))
      (node (ref "U8") (pin "3") (pinfunction "VOUT_3") (pintype "power_in"))
      (node (ref "U8") (pin "4") (pinfunction "FB_4") (pintype "input"))
    )
    (net (code "3") (name "/+3V3_2") (class "Default")
      (node (ref "+3V3_2") (pin "A") (pinfunction "A_A") (pintype "passive"))
      (node (ref "C14") (pin "1") (pinfunction "1_1") (pintype "passive"))
      (node (ref "C15") (pin "1") (pinfunction "1_1") (pintype "passive"))
      (node (ref "JP4") (pin "10") (pinfunction "10_10") (pintype "passive"))
      (node (ref "U4") (pin "1") (pinfunction "VOUT_2_1") (pintype "passive"))
      (node (ref "U4") (pin "2") (pinfunction "VOUT_3_2") (pintype "power_in"))
      (node (ref "U4") (pin "3") (pinfunction "VOUT_3") (pintype "power_in"))
      (node (ref "U4") (pin "4") (pinfunction "FB_4") (pintype "input"))
    )
    (net (code "4") (name "/+3V3_M") (class "Default")
      (node (ref "+3V3_M") (pin "A") (pinfunction "A_A") (pintype "passive"))
      (node (ref "JP4") (pin "6") (pinfunction "6_6") (pintype "passive"))
      (node (ref "U3") (pin "6") (pinfunction "OUT1_6") (pintype "bidirectional"))
      (node (ref "U3") (pin "7") (pinfunction "OUT2_7") (pintype "bidirectional"))
      (node (ref "U3") (pin "8") (pinfunction "OUT3_8") (pintype "bidirectional"))
    )
    (net (code "5") (name "/+5V") (class "Default")
      (node (ref "+5V") (pin "A") (pinfunction "A_A") (pintype "passive"))
      (node (ref "C21") (pin "1") (pinfunction "1_1") (pintype "passive"))
      (node (ref "C22") (pin "1") (pinfunction "1_1") (pintype "passive"))
      (node (ref "C24") (pin "1") (pinfunction "1_1") (pintype "passive"))
      (node (ref "JP4") (pin "4") (pinfunction "4_4") (pintype "passive"))
      (node (ref "R37") (pin "2") (pinfunction "2_2") (pintype "passive"))
      (node (ref "U7") (pin "3") (pinfunction "VOUT_3") (pintype "power_in"))
      (node (ref "U7") (pin "4") (pinfunction "VOUT_4") (pintype "power_in"))
      (node (ref "U7") (pin "7") (pinfunction "FB_7") (pintype "input"))
    )
    (net (code "6") (name "/+12V") (class "Default")
      (node (ref "+11V") (pin "A") (pinfunction "A_A") (pintype "passive"))
      (node (ref "C34") (pin "2") (pinfunction "2_2") (pintype "passive"))
      (node (ref "C36") (pin "2") (pinfunction "2_2") (pintype "passive"))
      (node (ref "C38") (pin "2") (pinfunction "2_2") (pintype "passive"))
      (node (ref "C39") (pin "2") (pinfunction "2_2") (pintype "passive"))
      (node (ref "JP4") (pin "2") (pinfunction "2_2") (pintype "passive"))
      (node (ref "R47") (pin "2") (pinfunction "2_2") (pintype "passive"))
      (node (ref "U12") (pin "P$14") (pinfunction "VOUT1_P$14") (pintype "bidirectional"))
      (node (ref "U12") (pin "P$15") (pinfunction "VOUT2_P$15") (pintype "bidirectional"))
      (node (ref "U12") (pin "P$16") (pinfunction "VOUT3_P$16") (pintype "bidirectional"))
    )
    (net (code "7") (name "/AVCC") (class "Default")
      (node (ref "C8") (pin "1") (pinfunction "1_1") (pintype "passive"))
      (node (ref "LF2") (pin "1") (pinfunction "1_1") (pintype "passive"))
      (node (ref "RT1") (pin "1") (pinfunction "1_1") (pintype "passive"))
      (node (ref "RT2") (pin "1") (pinfunction "1_1") (pintype "passive"))
      (node (ref "U1") (pin "48") (pinfunction "AVCC_48") (pintype "bidirectional"))
    )
    (net (code "8") (name "/AVCC1") (class "Default")
      (node (ref "LF3") (pin "1") (pinfunction "1_1") (pintype "passive"))
      (node (ref "U10") (pin "3") (pinfunction "VCC_3") (pintype "bidirectional"))
      (node (ref "U9") (pin "3") (pinfunction "VCC_3") (pintype "bidirectional"))
    )
    (net (code "9") (name "/AVCC2") (class "Default")
      (node (ref "C2") (pin "2") (pinfunction "2_2") (pintype "passive"))
      (node (ref "LF1") (pin "1") (pinfunction "1_1") (pintype "passive"))
      (node (ref "U2") (pin "8") (pinfunction "V+_8") (pintype "power_in"))
    )
    (net (code "10") (name "/A_EXT0") (class "Default")
      (node (ref "JP2") (pin "11") (pinfunction "11_11") (pintype "passive"))
      (node (ref "RT2") (pin "2") (pinfunction "2_2") (pintype "passive"))
      (node (ref "U1") (pin "10") (pinfunction "P1.4/TB0.1/UCA0STE/A4/C4_10") (pintype "bidirectional"))
    )
    (net (code "11") (name "/A_EXT1") (class "Default")
      (node (ref "JP2") (pin "9") (pinfunction "9_9") (pintype "passive"))
      (node (ref "RT1") (pin "2") (pinfunction "2_2") (pintype "passive"))
      (node (ref "U1") (pin "11") (pinfunction "P1.5/TB0.2/UCA0CLK/A5/C5_11") (pintype "bidirectional"))
    )
    (net (code "12") (name "/A_EXT2") (class "Default")
      (node (ref "JP2") (pin "7") (pinfunction "7_7") (pintype "passive"))
      (node (ref "U1") (pin "16") (pinfunction "P4.0/A8_16") (pintype "bidirectional"))
    )
    (net (code "13") (name "/A_EXT3") (class "Default")
      (node (ref "JP2") (pin "5") (pinfunction "5_5") (pintype "passive"))
      (node (ref "U1") (pin "17") (pinfunction "P4.1/A9_17") (pintype "bidirectional"))
    )
    (net (code "14") (name "/A_EXT4") (class "Default")
      (node (ref "JP2") (pin "3") (pinfunction "3_3") (pintype "passive"))
      (node (ref "U1") (pin "18") (pinfunction "P4.2/A10_18") (pintype "bidirectional"))
    )
    (net (code "15") (name "/A_EXT5") (class "Default")
      (node (ref "JP2") (pin "1") (pinfunction "1_1") (pintype "passive"))
      (node (ref "U1") (pin "19") (pinfunction "P4.3/A11_19") (pintype "bidirectional"))
    )
    (net (code "16") (name "/BAT+") (class "Default")
      (node (ref "JP6") (pin "2") (pinfunction "2_2") (pintype "passive"))
      (node (ref "R23") (pin "2") (pinfunction "2_2") (pintype "passive"))
      (node (ref "RS2") (pin "I2") (pinfunction "I2_I2") (pintype "bidirectional"))
      (node (ref "RS3") (pin "I1") (pinfunction "I1_I1") (pintype "bidirectional"))
    )
    (net (code "17") (name "/BAT_OUT") (class "Default")
      (node (ref "C13") (pin "1") (pinfunction "1_1") (pintype "passive"))
      (node (ref "C19") (pin "1") (pinfunction "1_1") (pintype "passive"))
      (node (ref "C23") (pin "1") (pinfunction "1_1") (pintype "passive"))
      (node (ref "C31") (pin "1") (pinfunction "1_1") (pintype "passive"))
      (node (ref "JP4") (pin "11") (pinfunction "11_11") (pintype "passive"))
      (node (ref "JP4") (pin "13") (pinfunction "13_13") (pintype "passive"))
      (node (ref "JP4") (pin "15") (pinfunction "15_15") (pintype "passive"))
      (node (ref "L5") (pin "P$1") (pinfunction "1_P$1") (pintype "passive"))
      (node (ref "Q7") (pin "5") (pinfunction "D_5") (pintype "passive"))
      (node (ref "Q7") (pin "6") (pinfunction "D_6") (pintype "passive"))
      (node (ref "Q7") (pin "7") (pinfunction "D_7") (pintype "passive"))
      (node (ref "Q7") (pin "8") (pinfunction "D_8") (pintype "passive"))
      (node (ref "RS3") (pin "I2") (pinfunction "I2_I2") (pintype "bidirectional"))
      (node (ref "U11") (pin "P$1") (pinfunction "VDD_P$1") (pintype "bidirectional"))
      (node (ref "U11") (pin "P1") (pinfunction "VDD_P1") (pintype "bidirectional"))
      (node (ref "U4") (pin "17") (pinfunction "VIN_2_17") (pintype "power_in"))
      (node (ref "U4") (pin "18") (pinfunction "VIN_3_18") (pintype "power_in"))
      (node (ref "U4") (pin "19") (pinfunction "VIN_19") (pintype "power_in"))
      (node (ref "U4") (pin "20") (pinfunction "VINA_20") (pintype "power_in"))
      (node (ref "U6") (pin "16") (pinfunction "EN_16") (pintype "input"))
      (node (ref "U6") (pin "17") (pinfunction "VIN_2_17") (pintype "power_in"))
      (node (ref "U6") (pin "18") (pinfunction "VIN_3_18") (pintype "power_in"))
      (node (ref "U6") (pin "19") (pinfunction "VIN_19") (pintype "power_in"))
      (node (ref "U6") (pin "20") (pinfunction "VINA_20") (pintype "power_in"))
      (node (ref "U7") (pin "10") (pinfunction "VIN_10") (pintype "input"))
      (node (ref "U8") (pin "17") (pinfunction "VIN_2_17") (pintype "power_in"))
      (node (ref "U8") (pin "18") (pinfunction "VIN_3_18") (pintype "power_in"))
      (node (ref "U8") (pin "19") (pinfunction "VIN_19") (pintype "power_in"))
      (node (ref "U8") (pin "20") (pinfunction "VINA_20") (pintype "power_in"))
    )
    (net (code "18") (name "/EN_3V3_1") (class "Default")
      (node (ref "R38") (pin "1") (pinfunction "1_1") (pintype "passive"))
      (node (ref "U1") (pin "7") (pinfunction "P3.3/A15/C15_7") (pintype "bidirectional"))
      (node (ref "U8") (pin "16") (pinfunction "EN_16") (pintype "input"))
    )
    (net (code "19") (name "/EN_3V3_2") (class "Default")
      (node (ref "R27") (pin "1") (pinfunction "1_1") (pintype "passive"))
      (node (ref "U1") (pin "8") (pinfunction "P4.7_8") (pintype "bidirectional"))
      (node (ref "U4") (pin "16") (pinfunction "EN_16") (pintype "input"))
    )
    (net (code "20") (name "/EN_3V3_M") (class "Default")
      (node (ref "R26") (pin "1") (pinfunction "1_1") (pintype "passive"))
      (node (ref "U1") (pin "6") (pinfunction "P3.2/A14/C14_6") (pintype "bidirectional"))
      (node (ref "U3") (pin "4") (pinfunction "EN_4") (pintype "bidirectional"))
    )
    (net (code "21") (name "/EN_5V") (class "Default")
      (node (ref "R36") (pin "2") (pinfunction "2_2") (pintype "passive"))
      (node (ref "U1") (pin "5") (pinfunction "P3.1/A13/C13_5") (pintype "bidirectional"))
      (node (ref "U7") (pin "9") (pinfunction "EN_9") (pintype "input"))
    )
    (net (code "22") (name "/EN_12V") (class "Default")
      (node (ref "R42") (pin "2") (pinfunction "2_2") (pintype "passive"))
      (node (ref "U1") (pin "4") (pinfunction "P3.0/A12/C12_4") (pintype "bidirectional"))
      (node (ref "U11") (pin "P$3") (pinfunction "IN_P$3") (pintype "bidirectional"))
      (node (ref "U11") (pin "P3") (pinfunction "IN_P3") (pintype "bidirectional"))
    )
    (net (code "23") (name "/EN_HEAT1") (class "Default")
      (node (ref "R16") (pin "2") (pinfunction "2_2") (pintype "passive"))
      (node (ref "R17") (pin "1") (pinfunction "1_1") (pintype "passive"))
      (node (ref "U1") (pin "12") (pinfunction "PJ.0/TDO_12") (pintype "bidirectional"))
    )
    (net (code "24") (name "/EN_HEAT2") (class "Default")
      (node (ref "R18") (pin "2") (pinfunction "2_2") (pintype "passive"))
      (node (ref "R19") (pin "1") (pinfunction "1_1") (pintype "passive"))
      (node (ref "U1") (pin "13") (pinfunction "PJ.1/TDI_13") (pintype "bidirectional"))
    )
    (net (code "25") (name "/EN_HEAT3") (class "Default")
      (node (ref "R20") (pin "2") (pinfunction "2_2") (pintype "passive"))
      (node (ref "R21") (pin "1") (pinfunction "1_1") (pintype "passive"))
      (node (ref "U1") (pin "14") (pinfunction "PJ.2/TMS_14") (pintype "bidirectional"))
    )
    (net (code "26") (name "/EN_SC") (class "Default")
      (node (ref "Q4") (pin "1") (pinfunction "G_1") (pintype "passive"))
      (node (ref "R28") (pin "1") (pinfunction "1_1") (pintype "passive"))
      (node (ref "R32") (pin "2") (pinfunction "2_2") (pintype "passive"))
      (node (ref "U1") (pin "27") (pinfunction "P3.4/TB0.3_27") (pintype "bidirectional"))
    )
    (net (code "27") (name "/HEAT1") (class "Default")
      (node (ref "JP4") (pin "12") (pinfunction "12_12") (pintype "passive"))
      (node (ref "Q1") (pin "5") (pinfunction "D_2_5") (pintype "passive"))
      (node (ref "Q1") (pin "6") (pinfunction "D_3_6") (pintype "passive"))
      (node (ref "Q1") (pin "7") (pinfunction "D_4_7") (pintype "passive"))
      (node (ref "Q1") (pin "8") (pinfunction "D_8") (pintype "passive"))
    )
    (net (code "28") (name "/HEAT2") (class "Default")
      (node (ref "JP4") (pin "14") (pinfunction "14_14") (pintype "passive"))
      (node (ref "Q2") (pin "5") (pinfunction "D_2_5") (pintype "passive"))
      (node (ref "Q2") (pin "6") (pinfunction "D_3_6") (pintype "passive"))
      (node (ref "Q2") (pin "7") (pinfunction "D_4_7") (pintype "passive"))
      (node (ref "Q2") (pin "8") (pinfunction "D_8") (pintype "passive"))
    )
    (net (code "29") (name "/HEAT3") (class "Default")
      (node (ref "JP4") (pin "16") (pinfunction "16_16") (pintype "passive"))
      (node (ref "Q3") (pin "5") (pinfunction "D_2_5") (pintype "passive"))
      (node (ref "Q3") (pin "6") (pinfunction "D_3_6") (pintype "passive"))
      (node (ref "Q3") (pin "7") (pinfunction "D_4_7") (pintype "passive"))
      (node (ref "Q3") (pin "8") (pinfunction "D_8") (pintype "passive"))
    )
    (net (code "30") (name "/I2C_SCL") (class "Default")
      (node (ref "JP3") (pin "2") (pinfunction "2_2") (pintype "passive"))
      (node (ref "U1") (pin "32") (pinfunction "P1.7/TB0.4/UCB0SOMI/UCB0SCL/TA1.0_32") (pintype "bidirectional"))
    )
    (net (code "31") (name "/I2C_SDA") (class "Default")
      (node (ref "JP3") (pin "1") (pinfunction "1_1") (pintype "passive"))
      (node (ref "U1") (pin "31") (pinfunction "P1.6/TB0.3/UCB0SIMO/UCB0SDA/TA0.0_31") (pintype "bidirectional"))
    )
    (net (code "32") (name "/I_IN") (class "Default")
      (node (ref "C9") (pin "2") (pinfunction "2_2") (pintype "passive"))
      (node (ref "R22") (pin "1") (pinfunction "1_1") (pintype "passive"))
      (node (ref "U1") (pin "2") (pinfunction "P1.1/TA0.2/A1/C1_2") (pintype "bidirectional"))
    )
    (net (code "33") (name "/I_OUT") (class "Default")
      (node (ref "C10") (pin "2") (pinfunction "2_2") (pintype "passive"))
      (node (ref "R24") (pin "1") (pinfunction "1_1") (pintype "passive"))
      (node (ref "U1") (pin "1") (pinfunction "P1.0/TA0.1/A0/C0_1") (pintype "bidirectional"))
    )
    (net (code "34") (name "/SC+") (class "Default")
      (node (ref "C40") (pin "2") (pinfunction "2_2") (pintype "passive"))
      (node (ref "JP5") (pin "2") (pinfunction "2_2") (pintype "passive"))
      (node (ref "Q5") (pin "5") (pinfunction "D_2_5") (pintype "passive"))
      (node (ref "Q5") (pin "6") (pinfunction "D_3_6") (pintype "passive"))
      (node (ref "Q5") (pin "7") (pinfunction "D_4_7") (pintype "passive"))
      (node (ref "Q5") (pin "8") (pinfunction "D_8") (pintype "passive"))
      (node (ref "R25") (pin "2") (pinfunction "2_2") (pintype "passive"))
      (node (ref "R28") (pin "2") (pinfunction "2_2") (pintype "passive"))
      (node (ref "R29") (pin "2") (pinfunction "2_2") (pintype "passive"))
      (node (ref "R30") (pin "2") (pinfunction "2_2") (pintype "passive"))
      (node (ref "R31") (pin "2") (pinfunction "2_2") (pintype "passive"))
      (node (ref "R39") (pin "2") (pinfunction "2_2") (pintype "passive"))
      (node (ref "R40") (pin "1") (pinfunction "1_1") (pintype "passive"))
    )
    (net (code "35") (name "/SC_OUT") (class "Default")
      (node (ref "C30") (pin "1") (pinfunction "1_1") (pintype "passive"))
      (node (ref "C41") (pin "1") (pinfunction "1_1") (pintype "passive"))
      (node (ref "C42") (pin "1") (pinfunction "1_1") (pintype "passive"))
      (node (ref "R35") (pin "2") (pinfunction "2_2") (pintype "passive"))
      (node (ref "R41") (pin "2") (pinfunction "2_2") (pintype "passive"))
      (node (ref "RS1") (pin "I2") (pinfunction "I2_I2") (pintype "bidirectional"))
      (node (ref "RS2") (pin "I1") (pinfunction "I1_I1") (pintype "bidirectional"))
    )
    (net (code "36") (name "/TS") (class "Default")
      (node (ref "RT3") (pin "2") (pinfunction "2_2") (pintype "passive"))
      (node (ref "RT4") (pin "1") (pinfunction "1_1") (pintype "passive"))
      (node (ref "RTH") (pin "2") (pinfunction "2_2") (pintype "passive"))
      (node (ref "U5") (pin "4") (pinfunction "TS_4") (pintype "input"))
    )
    (net (code "37") (name "/V_BAT") (class "Default")
      (node (ref "C1") (pin "2") (pinfunction "2_2") (pintype "passive"))
      (node (ref "R5") (pin "1") (pinfunction "1_1") (pintype "passive"))
      (node (ref "U1") (pin "9") (pinfunction "P1.3/TA1.2/UCB0STE/A3/C3_9") (pintype "bidirectional"))
    )
    (net (code "38") (name "/V_SC") (class "Default")
      (node (ref "C3") (pin "2") (pinfunction "2_2") (pintype "passive"))
      (node (ref "R7") (pin "1") (pinfunction "1_1") (pintype "passive"))
      (node (ref "U1") (pin "3") (pinfunction "P1.2/TA1.1/A2/C2_3") (pintype "bidirectional"))
    )
    (net (code "39") (name "AGND") (class "Default")
      (node (ref "C1") (pin "1") (pinfunction "1_1") (pintype "passive"))
      (node (ref "C10") (pin "1") (pinfunction "1_1") (pintype "passive"))
      (node (ref "C2") (pin "1") (pinfunction "1_1") (pintype "passive"))
      (node (ref "C3") (pin "1") (pinfunction "1_1") (pintype "passive"))
      (node (ref "C8") (pin "2") (pinfunction "2_2") (pintype "passive"))
      (node (ref "C9") (pin "1") (pinfunction "1_1") (pintype "passive"))
      (node (ref "JP2") (pin "10") (pinfunction "10_10") (pintype "passive"))
      (node (ref "JP2") (pin "12") (pinfunction "12_12") (pintype "passive"))
      (node (ref "JP2") (pin "2") (pinfunction "2_2") (pintype "passive"))
      (node (ref "JP2") (pin "4") (pinfunction "4_4") (pintype "passive"))
      (node (ref "JP2") (pin "6") (pinfunction "6_6") (pintype "passive"))
      (node (ref "JP2") (pin "8") (pinfunction "8_8") (pintype "passive"))
      (node (ref "R2") (pin "2") (pinfunction "2_2") (pintype "passive"))
      (node (ref "R3") (pin "1") (pinfunction "1_1") (pintype "passive"))
      (node (ref "R6") (pin "1") (pinfunction "1_1") (pintype "passive"))
      (node (ref "R9") (pin "2") (pinfunction "2_2") (pintype "passive"))
      (node (ref "U1") (pin "41") (pinfunction "AVSS_41") (pintype "bidirectional"))
      (node (ref "U1") (pin "44") (pinfunction "AVSS_44") (pintype "bidirectional"))
      (node (ref "U1") (pin "47") (pinfunction "AVSS_47") (pintype "bidirectional"))
      (node (ref "U10") (pin "1") (pinfunction "REF_1") (pintype "bidirectional"))
      (node (ref "U10") (pin "2") (pinfunction "GND_2") (pintype "bidirectional"))
      (node (ref "U2") (pin "4") (pinfunction "V-_4") (pintype "power_in"))
      (node (ref "U9") (pin "1") (pinfunction "REF_1") (pintype "bidirectional"))
      (node (ref "U9") (pin "2") (pinfunction "GND_2") (pintype "bidirectional"))
    )
    (net (code "40") (name "GND") (class "Default")
      (node (ref "C11") (pin "2") (pinfunction "2_2") (pintype "passive"))
      (node (ref "C12") (pin "2") (pinfunction "2_2") (pintype "passive"))
      (node (ref "C13") (pin "2") (pinfunction "2_2") (pintype "passive"))
      (node (ref "C14") (pin "2") (pinfunction "2_2") (pintype "passive"))
      (node (ref "C15") (pin "2") (pinfunction "2_2") (pintype "passive"))
      (node (ref "C16") (pin "2") (pinfunction "2_2") (pintype "passive"))
      (node (ref "C18") (pin "2") (pinfunction "2_2") (pintype "passive"))
      (node (ref "C19") (pin "2") (pinfunction "2_2") (pintype "passive"))
      (node (ref "C20") (pin "2") (pinfunction "2_2") (pintype "passive"))
      (node (ref "C21") (pin "2") (pinfunction "2_2") (pintype "passive"))
      (node (ref "C22") (pin "2") (pinfunction "2_2") (pintype "passive"))
      (node (ref "C23") (pin "2") (pinfunction "2_2") (pintype "passive"))
      (node (ref "C24") (pin "2") (pinfunction "2_2") (pintype "passive"))
      (node (ref "C25") (pin "2") (pinfunction "2_2") (pintype "passive"))
      (node (ref "C26") (pin "2") (pinfunction "2_2") (pintype "passive"))
      (node (ref "C27") (pin "2") (pinfunction "2_2") (pintype "passive"))
      (node (ref "C28") (pin "2") (pinfunction "2_2") (pintype "passive"))
      (node (ref "C31") (pin "2") (pinfunction "2_2") (pintype "passive"))
      (node (ref "C33") (pin "2") (pinfunction "2_2") (pintype "passive"))
      (node (ref "C34") (pin "1") (pinfunction "1_1") (pintype "passive"))
      (node (ref "C35") (pin "2") (pinfunction "2_2") (pintype "passive"))
      (node (ref "C36") (pin "1") (pinfunction "1_1") (pintype "passive"))
      (node (ref "C37") (pin "2") (pinfunction "2_2") (pintype "passive"))
      (node (ref "C38") (pin "1") (pinfunction "1_1") (pintype "passive"))
      (node (ref "C39") (pin "1") (pinfunction "1_1") (pintype "passive"))
      (node (ref "C4") (pin "-") (pinfunction "-_-") (pintype "passive"))
      (node (ref "C40") (pin "1") (pinfunction "1_1") (pintype "passive"))
      (node (ref "C41") (pin "2") (pinfunction "2_2") (pintype "passive"))
      (node (ref "C42") (pin "2") (pinfunction "2_2") (pintype "passive"))
      (node (ref "C43") (pin "2") (pinfunction "2_2") (pintype "passive"))
      (node (ref "C44") (pin "2") (pinfunction "2_2") (pintype "passive"))
      (node (ref "C45") (pin "2") (pinfunction "2_2") (pintype "passive"))
      (node (ref "C46") (pin "2") (pinfunction "2_2") (pintype "passive"))
      (node (ref "C5") (pin "2") (pinfunction "2_2") (pintype "passive"))
      (node (ref "C6") (pin "1") (pinfunction "1_1") (pintype "passive"))
      (node (ref "C7") (pin "1") (pinfunction "1_1") (pintype "passive"))
      (node (ref "J102") (pin "1") (pinfunction "1_1") (pintype "passive"))
      (node (ref "J103") (pin "1") (pinfunction "1_1") (pintype "passive"))
      (node (ref "J104") (pin "1") (pinfunction "1_1") (pintype "passive"))
      (node (ref "J105") (pin "1") (pinfunction "1_1") (pintype "passive"))
      (node (ref "J106") (pin "1") (pinfunction "1_1") (pintype "passive"))
      (node (ref "J107") (pin "1") (pinfunction "1_1") (pintype "passive"))
      (node (ref "JP4") (pin "1") (pinfunction "1_1") (pintype "passive"))
      (node (ref "JP4") (pin "3") (pinfunction "3_3") (pintype "passive"))
      (node (ref "JP4") (pin "5") (pinfunction "5_5") (pintype "passive"))
      (node (ref "JP4") (pin "7") (pinfunction "7_7") (pintype "passive"))
      (node (ref "JP4") (pin "9") (pinfunction "9_9") (pintype "passive"))
      (node (ref "JP5") (pin "1") (pinfunction "1_1") (pintype "passive"))
      (node (ref "JP6") (pin "1") (pinfunction "1_1") (pintype "passive"))
      (node (ref "Q1") (pin "1") (pinfunction "S_2_1") (pintype "passive"))
      (node (ref "Q1") (pin "2") (pinfunction "S_3_2") (pintype "passive"))
      (node (ref "Q1") (pin "3") (pinfunction "S_3") (pintype "passive"))
      (node (ref "Q2") (pin "1") (pinfunction "S_2_1") (pintype "passive"))
      (node (ref "Q2") (pin "2") (pinfunction "S_3_2") (pintype "passive"))
      (node (ref "Q2") (pin "3") (pinfunction "S_3") (pintype "passive"))
      (node (ref "Q3") (pin "1") (pinfunction "S_2_1") (pintype "passive"))
      (node (ref "Q3") (pin "2") (pinfunction "S_3_2") (pintype "passive"))
      (node (ref "Q3") (pin "3") (pinfunction "S_3") (pintype "passive"))
      (node (ref "Q4") (pin "2") (pinfunction "S_2") (pintype "passive"))
      (node (ref "Q6") (pin "1") (pinfunction "S_2_1") (pintype "passive"))
      (node (ref "Q6") (pin "2") (pinfunction "S_3_2") (pintype "passive"))
      (node (ref "Q6") (pin "3") (pinfunction "S_3") (pintype "passive"))
      (node (ref "R17") (pin "2") (pinfunction "2_2") (pintype "passive"))
      (node (ref "R19") (pin "2") (pinfunction "2_2") (pintype "passive"))
      (node (ref "R21") (pin "2") (pinfunction "2_2") (pintype "passive"))
      (node (ref "R27") (pin "2") (pinfunction "2_2") (pintype "passive"))
      (node (ref "R32") (pin "1") (pinfunction "1_1") (pintype "passive"))
      (node (ref "R33") (pin "1") (pinfunction "1_1") (pintype "passive"))
      (node (ref "R34") (pin "1") (pinfunction "1_1") (pintype "passive"))
      (node (ref "R36") (pin "1") (pinfunction "1_1") (pintype "passive"))
      (node (ref "R38") (pin "2") (pinfunction "2_2") (pintype "passive"))
      (node (ref "R42") (pin "1") (pinfunction "1_1") (pintype "passive"))
      (node (ref "R44") (pin "1") (pinfunction "1_1") (pintype "passive"))
      (node (ref "R46") (pin "1") (pinfunction "1_1") (pintype "passive"))
      (node (ref "R48") (pin "2") (pinfunction "2_2") (pintype "passive"))
      (node (ref "RT4") (pin "2") (pinfunction "2_2") (pintype "passive"))
      (node (ref "RTH") (pin "1") (pinfunction "1_1") (pintype "passive"))
      (node (ref "U1") (pin "36") (pinfunction "DVSS_36") (pintype "bidirectional"))
      (node (ref "U1") (pin "VSS_QFN") (pinfunction "VSS_QFN_VSS_QFN") (pintype "bidirectional"))
      (node (ref "U11") (pin "P$2") (pinfunction "GND_P$2") (pintype "bidirectional"))
      (node (ref "U11") (pin "P2") (pinfunction "GND_P2") (pintype "bidirectional"))
      (node (ref "U12") (pin "P$20") (pinfunction "AGND_P$20") (pintype "bidirectional"))
      (node (ref "U12") (pin "PGND1") (pinfunction "PGND_PGND1") (pintype "bidirectional"))
      (node (ref "U12") (pin "PGND10") (pinfunction "PGND_PGND10") (pintype "bidirectional"))
      (node (ref "U12") (pin "PGND11") (pinfunction "PGND_PGND11") (pintype "bidirectional"))
      (node (ref "U12") (pin "PGND12") (pinfunction "PGND_PGND12") (pintype "bidirectional"))
      (node (ref "U12") (pin "PGND2") (pinfunction "PGND_PGND2") (pintype "bidirectional"))
      (node (ref "U12") (pin "PGND3") (pinfunction "PGND_PGND3") (pintype "bidirectional"))
      (node (ref "U12") (pin "PGND4") (pinfunction "PGND_PGND4") (pintype "bidirectional"))
      (node (ref "U12") (pin "PGND5") (pinfunction "PGND_PGND5") (pintype "bidirectional"))
      (node (ref "U12") (pin "PGND6") (pinfunction "PGND_PGND6") (pintype "bidirectional"))
      (node (ref "U12") (pin "PGND7") (pinfunction "PGND_PGND7") (pintype "bidirectional"))
      (node (ref "U12") (pin "PGND8") (pinfunction "PGND_PGND8") (pintype "bidirectional"))
      (node (ref "U12") (pin "PGND9") (pinfunction "PGND_PGND9") (pintype "bidirectional"))
      (node (ref "U3") (pin "1") (pinfunction "GND_1") (pintype "bidirectional"))
      (node (ref "U4") (pin "10") (pinfunction "PGND_3_10") (pintype "power_in"))
      (node (ref "U4") (pin "11") (pinfunction "PGND_11") (pintype "power_in"))
      (node (ref "U4") (pin "12") (pinfunction "GND_12") (pintype "power_in"))
      (node (ref "U4") (pin "8") (pinfunction "PFM_PWM_8") (pintype "input"))
      (node (ref "U4") (pin "9") (pinfunction "PGND_2_9") (pintype "power_in"))
      (node (ref "U5") (pin "11") (pinfunction "GND_11") (pintype "power_in"))
      (node (ref "U5") (pin "17") (pinfunction "EPAD_17") (pintype "power_in"))
      (node (ref "U5") (pin "7") (pinfunction "TERM_EN_7") (pintype "input"))
      (node (ref "U5") (pin "V") (pinfunction "EPAD_V") (pintype "power_in"))
      (node (ref "U5") (pin "V_1") (pinfunction "EPAD_V_1") (pintype "power_in"))
      (node (ref "U5") (pin "V_2") (pinfunction "EPAD_V_2") (pintype "power_in"))
      (node (ref "U5") (pin "V_3") (pinfunction "EPAD_V_3") (pintype "power_in"))
      (node (ref "U6") (pin "10") (pinfunction "PGND_3_10") (pintype "power_in"))
      (node (ref "U6") (pin "11") (pinfunction "PGND_11") (pintype "power_in"))
      (node (ref "U6") (pin "12") (pinfunction "GND_12") (pintype "power_in"))
      (node (ref "U6") (pin "8") (pinfunction "PFM_PWM_8") (pintype "input"))
      (node (ref "U6") (pin "9") (pinfunction "PGND_2_9") (pintype "power_in"))
      (node (ref "U7") (pin "EXPAD") (pinfunction "GND_EXPAD") (pintype "power_in"))
      (node (ref "U7") (pin "GND1") (pinfunction "GND1_GND1") (pintype "power_in"))
      (node (ref "U7") (pin "GND2") (pinfunction "GND2_GND2") (pintype "power_in"))
      (node (ref "U7") (pin "GND3") (pinfunction "GND3_GND3") (pintype "power_in"))
      (node (ref "U7") (pin "GND4") (pinfunction "GND4_GND4") (pintype "power_in"))
      (node (ref "U7") (pin "GND5") (pinfunction "GND5_GND5") (pintype "power_in"))
      (node (ref "U8") (pin "10") (pinfunction "PGND_3_10") (pintype "power_in"))
      (node (ref "U8") (pin "11") (pinfunction "PGND_11") (pintype "power_in"))
      (node (ref "U8") (pin "12") (pinfunction "GND_12") (pintype "power_in"))
      (node (ref "U8") (pin "8") (pinfunction "PFM_PWM_8") (pintype "input"))
      (node (ref "U8") (pin "9") (pinfunction "PGND_2_9") (pintype "power_in"))
      (node (ref "VCC_GND") (pin "2") (pinfunction "2_2") (pintype "passive"))
      (node (ref "X1") (pin "P3") (pinfunction "GND_P3") (pintype "power_in"))
    )
    (net (code "41") (name "Net-(+3V3_1-PadC)") (class "Default")
      (node (ref "+3V3_1") (pin "C") (pinfunction "C_C") (pintype "passive"))
      (node (ref "R12") (pin "2") (pinfunction "2_2") (pintype "passive"))
    )
    (net (code "42") (name "Net-(+3V3_2-PadC)") (class "Default")
      (node (ref "+3V3_2") (pin "C") (pinfunction "C_C") (pintype "passive"))
      (node (ref "R13") (pin "2") (pinfunction "2_2") (pintype "passive"))
    )
    (net (code "43") (name "Net-(+3V3_M-PadC)") (class "Default")
      (node (ref "+3V3_M") (pin "C") (pinfunction "C_C") (pintype "passive"))
      (node (ref "R11") (pin "2") (pinfunction "2_2") (pintype "passive"))
    )
    (net (code "44") (name "Net-(+5V-PadC)") (class "Default")
      (node (ref "+5V") (pin "C") (pinfunction "C_C") (pintype "passive"))
      (node (ref "R14") (pin "2") (pinfunction "2_2") (pintype "passive"))
    )
    (net (code "45") (name "Net-(+11V-PadC)") (class "Default")
      (node (ref "+11V") (pin "C") (pinfunction "C_C") (pintype "passive"))
      (node (ref "R15") (pin "2") (pinfunction "2_2") (pintype "passive"))
    )
    (net (code "46") (name "Net-(C27-Pad1)") (class "Default")
      (node (ref "C27") (pin "1") (pinfunction "1_1") (pintype "passive"))
      (node (ref "R39") (pin "1") (pinfunction "1_1") (pintype "passive"))
    )
    (net (code "47") (name "Net-(C37-Pad1)") (class "Default")
      (node (ref "C37") (pin "1") (pinfunction "1_1") (pintype "passive"))
      (node (ref "R45") (pin "1") (pinfunction "1_1") (pintype "passive"))
    )
    (net (code "48") (name "Net-(D1-A1)") (class "Default")
      (node (ref "C16") (pin "1") (pinfunction "1_1") (pintype "passive"))
      (node (ref "D1") (pin "1") (pinfunction "A1_1") (pintype "passive"))
      (node (ref "D1") (pin "2") (pinfunction "A2_2") (pintype "passive"))
      (node (ref "U5") (pin "12") (pinfunction "REGN_12") (pintype "power_in"))
    )
    (net (code "49") (name "Net-(D1-CC)") (class "Default")
      (node (ref "C29") (pin "2") (pinfunction "2_2") (pintype "passive"))
      (node (ref "D1") (pin "3") (pinfunction "CC_3") (pintype "passive"))
      (node (ref "U5") (pin "16") (pinfunction "BTST_16") (pintype "power_in"))
    )
    (net (code "50") (name "Net-(J100-Pad2)") (class "Default")
      (node (ref "J100") (pin "2") (pinfunction "2_2") (pintype "passive"))
      (node (ref "STAT1") (pin "C") (pinfunction "C_C") (pintype "passive"))
    )
    (net (code "51") (name "Net-(J101-Pad2)") (class "Default")
      (node (ref "J101") (pin "2") (pinfunction "2_2") (pintype "passive"))
      (node (ref "STAT2") (pin "C") (pinfunction "C_C") (pintype "passive"))
    )
    (net (code "52") (name "Net-(J102-Pad2)") (class "Default")
      (node (ref "J102") (pin "2") (pinfunction "2_2") (pintype "passive"))
      (node (ref "R15") (pin "1") (pinfunction "1_1") (pintype "passive"))
    )
    (net (code "53") (name "Net-(J103-Pad2)") (class "Default")
      (node (ref "J103") (pin "2") (pinfunction "2_2") (pintype "passive"))
      (node (ref "R14") (pin "1") (pinfunction "1_1") (pintype "passive"))
    )
    (net (code "54") (name "Net-(J104-Pad2)") (class "Default")
      (node (ref "J104") (pin "2") (pinfunction "2_2") (pintype "passive"))
      (node (ref "R13") (pin "1") (pinfunction "1_1") (pintype "passive"))
    )
    (net (code "55") (name "Net-(J105-Pad2)") (class "Default")
      (node (ref "J105") (pin "2") (pinfunction "2_2") (pintype "passive"))
      (node (ref "R12") (pin "1") (pinfunction "1_1") (pintype "passive"))
    )
    (net (code "56") (name "Net-(J106-Pad2)") (class "Default")
      (node (ref "J106") (pin "2") (pinfunction "2_2") (pintype "passive"))
      (node (ref "R11") (pin "1") (pinfunction "1_1") (pintype "passive"))
    )
    (net (code "57") (name "Net-(J107-Pad2)") (class "Default")
      (node (ref "J107") (pin "2") (pinfunction "2_2") (pintype "passive"))
      (node (ref "R10") (pin "1") (pinfunction "1_1") (pintype "passive"))
    )
    (net (code "58") (name "Net-(L1-1)") (class "Default")
      (node (ref "L1") (pin "P$1") (pinfunction "1_P$1") (pintype "passive"))
      (node (ref "U4") (pin "13") (pinfunction "L1_2_13") (pintype "passive"))
      (node (ref "U4") (pin "14") (pinfunction "L1_3_14") (pintype "passive"))
      (node (ref "U4") (pin "15") (pinfunction "L1_15") (pintype "passive"))
    )
    (net (code "59") (name "Net-(L1-2)") (class "Default")
      (node (ref "L1") (pin "P$2") (pinfunction "2_P$2") (pintype "passive"))
      (node (ref "U4") (pin "5") (pinfunction "L2_2_5") (pintype "power_in"))
      (node (ref "U4") (pin "6") (pinfunction "L2_3_6") (pintype "power_in"))
      (node (ref "U4") (pin "7") (pinfunction "L2_7") (pintype "power_in"))
    )
    (net (code "60") (name "Net-(L2-1)") (class "Default")
      (node (ref "L2") (pin "P$1") (pinfunction "1_P$1") (pintype "passive"))
      (node (ref "U8") (pin "13") (pinfunction "L1_2_13") (pintype "passive"))
      (node (ref "U8") (pin "14") (pinfunction "L1_3_14") (pintype "passive"))
      (node (ref "U8") (pin "15") (pinfunction "L1_15") (pintype "passive"))
    )
    (net (code "61") (name "Net-(L2-2)") (class "Default")
      (node (ref "L2") (pin "P$2") (pinfunction "2_P$2") (pintype "passive"))
      (node (ref "U8") (pin "5") (pinfunction "L2_2_5") (pintype "power_in"))
      (node (ref "U8") (pin "6") (pinfunction "L2_3_6") (pintype "power_in"))
      (node (ref "U8") (pin "7") (pinfunction "L2_7") (pintype "power_in"))
    )
    (net (code "62") (name "Net-(L3-1)") (class "Default")
      (node (ref "L3") (pin "P$1") (pinfunction "1_P$1") (pintype "passive"))
      (node (ref "U6") (pin "13") (pinfunction "L1_2_13") (pintype "passive"))
      (node (ref "U6") (pin "14") (pinfunction "L1_3_14") (pintype "passive"))
      (node (ref "U6") (pin "15") (pinfunction "L1_15") (pintype "passive"))
    )
    (net (code "63") (name "Net-(L3-2)") (class "Default")
      (node (ref "L3") (pin "P$2") (pinfunction "2_P$2") (pintype "passive"))
      (node (ref "U6") (pin "5") (pinfunction "L2_2_5") (pintype "power_in"))
      (node (ref "U6") (pin "6") (pinfunction "L2_3_6") (pintype "power_in"))
      (node (ref "U6") (pin "7") (pinfunction "L2_7") (pintype "power_in"))
    )
    (net (code "64") (name "Net-(L4-Pad2)") (class "Default")
      (node (ref "L4") (pin "2") (pinfunction "2_2") (pintype "passive"))
      (node (ref "RS1") (pin "I1") (pinfunction "I1_I1") (pintype "bidirectional"))
    )
    (net (code "65") (name "Net-(L5-2)") (class "Default")
      (node (ref "L5") (pin "P$2") (pinfunction "2_P$2") (pintype "passive"))
      (node (ref "U7") (pin "1") (pinfunction "SW_1") (pintype "power_in"))
      (node (ref "U7") (pin "2") (pinfunction "SW_2") (pintype "power_in"))
    )
    (net (code "66") (name "Net-(L6-1)") (class "Default")
      (node (ref "C43") (pin "1") (pinfunction "1_1") (pintype "passive"))
      (node (ref "C44") (pin "1") (pinfunction "1_1") (pintype "passive"))
      (node (ref "C45") (pin "1") (pinfunction "1_1") (pintype "passive"))
      (node (ref "L6") (pin "P$1") (pinfunction "1_P$1") (pintype "passive"))
      (node (ref "Q7") (pin "1") (pinfunction "S_1") (pintype "passive"))
      (node (ref "Q7") (pin "2") (pinfunction "S_2") (pintype "passive"))
      (node (ref "Q7") (pin "3") (pinfunction "S_3") (pintype "passive"))
      (node (ref "U12") (pin "P$2") (pinfunction "EN_P$2") (pintype "bidirectional"))
      (node (ref "U12") (pin "P$9") (pinfunction "VIN_P$9") (pintype "bidirectional"))
    )
    (net (code "67") (name "Net-(L6-2)") (class "Default")
      (node (ref "C32") (pin "1") (pinfunction "1_1") (pintype "passive"))
      (node (ref "L6") (pin "P$2") (pinfunction "2_P$2") (pintype "passive"))
      (node (ref "R43") (pin "2") (pinfunction "2_2") (pintype "passive"))
      (node (ref "U12") (pin "P$4") (pinfunction "SW1_P$4") (pintype "bidirectional"))
      (node (ref "U12") (pin "P$5") (pinfunction "SW2_P$5") (pintype "bidirectional"))
      (node (ref "U12") (pin "P$6") (pinfunction "SW3_P$6") (pintype "bidirectional"))
      (node (ref "U12") (pin "P$7") (pinfunction "SW4_P$7") (pintype "bidirectional"))
    )
    (net (code "68") (name "Net-(Q1-G)") (class "Default")
      (node (ref "Q1") (pin "4") (pinfunction "G_4") (pintype "passive"))
      (node (ref "R16") (pin "1") (pinfunction "1_1") (pintype "passive"))
    )
    (net (code "69") (name "Net-(Q2-G)") (class "Default")
      (node (ref "Q2") (pin "4") (pinfunction "G_4") (pintype "passive"))
      (node (ref "R18") (pin "1") (pinfunction "1_1") (pintype "passive"))
    )
    (net (code "70") (name "Net-(Q3-G)") (class "Default")
      (node (ref "Q3") (pin "4") (pinfunction "G_4") (pintype "passive"))
      (node (ref "R20") (pin "1") (pinfunction "1_1") (pintype "passive"))
    )
    (net (code "71") (name "Net-(Q4-D)") (class "Default")
      (node (ref "Q4") (pin "3") (pinfunction "D_3") (pintype "passive"))
      (node (ref "R29") (pin "1") (pinfunction "1_1") (pintype "passive"))
      (node (ref "R33") (pin "2") (pinfunction "2_2") (pintype "passive"))
      (node (ref "U5") (pin "2") (pinfunction "MPPSET_2") (pintype "input"))
    )
    (net (code "72") (name "Net-(Q5-G)") (class "Default")
      (node (ref "Q5") (pin "4") (pinfunction "G_4") (pintype "passive"))
      (node (ref "U5") (pin "15") (pinfunction "HIDRV_15") (pintype "output"))
    )
    (net (code "73") (name "Net-(Q5-S)") (class "Default")
      (node (ref "C29") (pin "1") (pinfunction "1_1") (pintype "passive"))
      (node (ref "L4") (pin "1") (pinfunction "1_1") (pintype "passive"))
      (node (ref "Q5") (pin "1") (pinfunction "S_2_1") (pintype "passive"))
      (node (ref "Q5") (pin "2") (pinfunction "S_3_2") (pintype "passive"))
      (node (ref "Q5") (pin "3") (pinfunction "S_3") (pintype "passive"))
      (node (ref "Q6") (pin "5") (pinfunction "D_2_5") (pintype "passive"))
      (node (ref "Q6") (pin "6") (pinfunction "D_3_6") (pintype "passive"))
      (node (ref "Q6") (pin "7") (pinfunction "D_4_7") (pintype "passive"))
      (node (ref "Q6") (pin "8") (pinfunction "D_8") (pintype "passive"))
      (node (ref "U5") (pin "14") (pinfunction "PH_14") (pintype "power_in"))
    )
    (net (code "74") (name "Net-(Q6-G)") (class "Default")
      (node (ref "Q6") (pin "4") (pinfunction "G_4") (pintype "passive"))
      (node (ref "U5") (pin "13") (pinfunction "LODRV_13") (pintype "output"))
    )
    (net (code "75") (name "Net-(Q7A-G)") (class "Default")
      (node (ref "Q7") (pin "4") (pinfunction "G_4") (pintype "passive"))
      (node (ref "U11") (pin "P$4") (pinfunction "OUT_P$4") (pintype "bidirectional"))
      (node (ref "U11") (pin "P4") (pinfunction "OUT_P4") (pintype "bidirectional"))
    )
    (net (code "76") (name "Net-(R10-Pad2)") (class "Default")
      (node (ref "R10") (pin "2") (pinfunction "2_2") (pintype "passive"))
      (node (ref "VCC") (pin "C") (pinfunction "C_C") (pintype "passive"))
    )
    (net (code "77") (name "Net-(R30-Pad1)") (class "Default")
      (node (ref "R30") (pin "1") (pinfunction "1_1") (pintype "passive"))
      (node (ref "STAT2") (pin "A") (pinfunction "A_A") (pintype "passive"))
    )
    (net (code "78") (name "Net-(R31-Pad1)") (class "Default")
      (node (ref "R31") (pin "1") (pinfunction "1_1") (pintype "passive"))
      (node (ref "STAT1") (pin "A") (pinfunction "A_A") (pintype "passive"))
    )
    (net (code "79") (name "Net-(U1-LFXIN)") (class "Default")
      (node (ref "C6") (pin "2") (pinfunction "2_2") (pintype "passive"))
      (node (ref "U1") (pin "45") (pinfunction "LFXIN_45") (pintype "bidirectional"))
      (node (ref "X1") (pin "P2") (pinfunction "2_P2") (pintype "bidirectional"))
    )
    (net (code "80") (name "Net-(U1-LFXOUT)") (class "Default")
      (node (ref "C7") (pin "2") (pinfunction "2_2") (pintype "passive"))
      (node (ref "U1") (pin "46") (pinfunction "LFXOUT_46") (pintype "bidirectional"))
      (node (ref "X1") (pin "P1") (pinfunction "1_P1") (pintype "bidirectional"))
    )
    (net (code "81") (name "Net-(U1-P2.0{slash}TB0.6{slash}UCA0TXD{slash}UCA0SIMO)") (class "Default")
      (node (ref "DIGITAL") (pin "4") (pinfunction "4_4") (pintype "passive"))
      (node (ref "U1") (pin "24") (pinfunction "P2.0/TB0.6/UCA0TXD/UCA0SIMO_24") (pintype "bidirectional"))
    )
    (net (code "82") (name "Net-(U1-P2.1{slash}TB0.0{slash}UCA0RXD{slash}UCA0SOMI)") (class "Default")
      (node (ref "DIGITAL") (pin "3") (pinfunction "3_3") (pintype "passive"))
      (node (ref "U1") (pin "25") (pinfunction "P2.1/TB0.0/UCA0RXD/UCA0SOMI_25") (pintype "bidirectional"))
    )
    (net (code "83") (name "Net-(U1-P2.3{slash}TA0.0{slash}UCA1STE{slash}A6)") (class "Default")
      (node (ref "DIGITAL") (pin "2") (pinfunction "2_2") (pintype "passive"))
      (node (ref "U1") (pin "39") (pinfunction "P2.3/TA0.0/UCA1STE/A6_39") (pintype "bidirectional"))
    )
    (net (code "84") (name "Net-(U1-P2.4{slash}TA1.0{slash}UCA1CLK{slash}A7)") (class "Default")
      (node (ref "DIGITAL") (pin "1") (pinfunction "1_1") (pintype "passive"))
      (node (ref "U1") (pin "40") (pinfunction "P2.4/TA1.0/UCA1CLK/A7_40") (pintype "bidirectional"))
    )
    (net (code "85") (name "Net-(U1-P2.5{slash}TB0.0{slash}UCA1TXD{slash}UCA1SIMO)") (class "Default")
      (node (ref "DIGITAL") (pin "6") (pinfunction "6_6") (pintype "passive"))
      (node (ref "U1") (pin "20") (pinfunction "P2.5/TB0.0/UCA1TXD/UCA1SIMO_20") (pintype "bidirectional"))
    )
    (net (code "86") (name "Net-(U1-P2.6{slash}TB0.1{slash}UCA1RXD{slash}UCA1SOMI)") (class "Default")
      (node (ref "DIGITAL") (pin "5") (pinfunction "5_5") (pintype "passive"))
      (node (ref "U1") (pin "21") (pinfunction "P2.6/TB0.1/UCA1RXD/UCA1SOMI_21") (pintype "bidirectional"))
    )
    (net (code "87") (name "Net-(U1-RST{slash}SBWTDIO)") (class "Default")
      (node (ref "JP1") (pin "1") (pinfunction "1_1") (pintype "passive"))
      (node (ref "R1") (pin "1") (pinfunction "1_1") (pintype "passive"))
      (node (ref "U1") (pin "23") (pinfunction "RST/SBWTDIO_23") (pintype "bidirectional"))
    )
    (net (code "88") (name "Net-(U1-TEST{slash}SBWTCK)") (class "Default")
      (node (ref "JP1") (pin "2") (pinfunction "2_2") (pintype "passive"))
      (node (ref "U1") (pin "22") (pinfunction "TEST/SBWTCK_22") (pintype "bidirectional"))
    )
    (net (code "89") (name "Net-(U2A-+IN)") (class "Default")
      (node (ref "R23") (pin "1") (pinfunction "1_1") (pintype "passive"))
      (node (ref "R3") (pin "2") (pinfunction "2_2") (pintype "passive"))
      (node (ref "U2") (pin "3") (pinfunction "+IN_3") (pintype "input"))
    )
    (net (code "90") (name "Net-(U2A--IN)") (class "Default")
      (node (ref "R2") (pin "1") (pinfunction "1_1") (pintype "passive"))
      (node (ref "R4") (pin "2") (pinfunction "2_2") (pintype "passive"))
      (node (ref "U2") (pin "2") (pinfunction "-IN_2") (pintype "input"))
    )
    (net (code "91") (name "Net-(U2A-OUT)") (class "Default")
      (node (ref "R4") (pin "1") (pinfunction "1_1") (pintype "passive"))
      (node (ref "R5") (pin "2") (pinfunction "2_2") (pintype "passive"))
      (node (ref "U2") (pin "1") (pinfunction "OUT_1") (pintype "output"))
    )
    (net (code "92") (name "Net-(U2B-+IN)") (class "Default")
      (node (ref "R25") (pin "1") (pinfunction "1_1") (pintype "passive"))
      (node (ref "R6") (pin "2") (pinfunction "2_2") (pintype "passive"))
      (node (ref "U2") (pin "5") (pinfunction "+IN_5") (pintype "input"))
    )
    (net (code "93") (name "Net-(U2B--IN)") (class "Default")
      (node (ref "R8") (pin "2") (pinfunction "2_2") (pintype "passive"))
      (node (ref "R9") (pin "1") (pinfunction "1_1") (pintype "passive"))
      (node (ref "U2") (pin "6") (pinfunction "-IN_6") (pintype "input"))
    )
    (net (code "94") (name "Net-(U2B-OUT)") (class "Default")
      (node (ref "R7") (pin "2") (pinfunction "2_2") (pintype "passive"))
      (node (ref "R8") (pin "1") (pinfunction "1_1") (pintype "passive"))
      (node (ref "U2") (pin "7") (pinfunction "OUT_7") (pintype "output"))
    )
    (net (code "95") (name "Net-(U5-SRN)") (class "Default")
      (node (ref "C17") (pin "1") (pinfunction "1_1") (pintype "passive"))
      (node (ref "RS1") (pin "V2") (pinfunction "V2_V2") (pintype "bidirectional"))
      (node (ref "U5") (pin "9") (pinfunction "SRN_9") (pintype "input"))
    )
    (net (code "96") (name "Net-(U5-SRP)") (class "Default")
      (node (ref "C17") (pin "2") (pinfunction "2_2") (pintype "passive"))
      (node (ref "RS1") (pin "V1") (pinfunction "V1_V1") (pintype "bidirectional"))
      (node (ref "U5") (pin "10") (pinfunction "SRP_10") (pintype "bidirectional"))
    )
    (net (code "97") (name "Net-(U5-STAT1)") (class "Default")
      (node (ref "J100") (pin "1") (pinfunction "1_1") (pintype "passive"))
      (node (ref "U5") (pin "3") (pinfunction "STAT1_3") (pintype "output"))
    )
    (net (code "98") (name "Net-(U5-STAT2)") (class "Default")
      (node (ref "J101") (pin "1") (pinfunction "1_1") (pintype "passive"))
      (node (ref "U5") (pin "5") (pinfunction "STAT2_5") (pintype "output"))
    )
    (net (code "99") (name "Net-(U5-VCC)") (class "Default")
      (node (ref "C28") (pin "1") (pinfunction "1_1") (pintype "passive"))
      (node (ref "R40") (pin "2") (pinfunction "2_2") (pintype "passive"))
      (node (ref "U5") (pin "1") (pinfunction "VCC_1") (pintype "power_in"))
    )
    (net (code "100") (name "Net-(U5-VFB)") (class "Default")
      (node (ref "C30") (pin "2") (pinfunction "2_2") (pintype "passive"))
      (node (ref "R34") (pin "2") (pinfunction "2_2") (pintype "passive"))
      (node (ref "R35") (pin "1") (pinfunction "1_1") (pintype "passive"))
      (node (ref "R41") (pin "1") (pinfunction "1_1") (pintype "passive"))
      (node (ref "U5") (pin "8") (pinfunction "VFB_8") (pintype "input"))
    )
    (net (code "101") (name "Net-(U5-VREF)") (class "Default")
      (node (ref "C18") (pin "1") (pinfunction "1_1") (pintype "passive"))
      (node (ref "RT3") (pin "1") (pinfunction "1_1") (pintype "passive"))
      (node (ref "U5") (pin "6") (pinfunction "VREF_6") (pintype "power_in"))
    )
    (net (code "102") (name "Net-(U7-PG)") (class "Default")
      (node (ref "R37") (pin "1") (pinfunction "1_1") (pintype "passive"))
      (node (ref "U7") (pin "5") (pinfunction "PG_5") (pintype "output"))
    )
    (net (code "103") (name "Net-(U7-SS)") (class "Default")
      (node (ref "C20") (pin "1") (pinfunction "1_1") (pintype "passive"))
      (node (ref "U7") (pin "6") (pinfunction "SS_6") (pintype "bidirectional"))
    )
    (net (code "104") (name "Net-(U9-IN+)") (class "Default")
      (node (ref "RS2") (pin "V1") (pinfunction "V1_V1") (pintype "bidirectional"))
      (node (ref "U9") (pin "4") (pinfunction "IN+_4") (pintype "bidirectional"))
    )
    (net (code "105") (name "Net-(U9-IN-)") (class "Default")
      (node (ref "RS2") (pin "V2") (pinfunction "V2_V2") (pintype "bidirectional"))
      (node (ref "U9") (pin "5") (pinfunction "IN-_5") (pintype "bidirectional"))
    )
    (net (code "106") (name "Net-(U9-OUT)") (class "Default")
      (node (ref "R22") (pin "2") (pinfunction "2_2") (pintype "passive"))
      (node (ref "U9") (pin "6") (pinfunction "OUT_6") (pintype "bidirectional"))
    )
    (net (code "107") (name "Net-(U10-IN+)") (class "Default")
      (node (ref "RS3") (pin "V1") (pinfunction "V1_V1") (pintype "bidirectional"))
      (node (ref "U10") (pin "4") (pinfunction "IN+_4") (pintype "bidirectional"))
    )
    (net (code "108") (name "Net-(U10-IN-)") (class "Default")
      (node (ref "RS3") (pin "V2") (pinfunction "V2_V2") (pintype "bidirectional"))
      (node (ref "U10") (pin "5") (pinfunction "IN-_5") (pintype "bidirectional"))
    )
    (net (code "109") (name "Net-(U10-OUT)") (class "Default")
      (node (ref "R24") (pin "2") (pinfunction "2_2") (pintype "passive"))
      (node (ref "U10") (pin "6") (pinfunction "OUT_6") (pintype "bidirectional"))
    )
    (net (code "110") (name "Net-(U12-BOOT)") (class "Default")
      (node (ref "C32") (pin "2") (pinfunction "2_2") (pintype "passive"))
      (node (ref "U12") (pin "P$8") (pinfunction "BOOT_P$8") (pintype "bidirectional"))
    )
    (net (code "111") (name "Net-(U12-COMP)") (class "Default")
      (node (ref "C35") (pin "1") (pinfunction "1_1") (pintype "passive"))
      (node (ref "R45") (pin "2") (pinfunction "2_2") (pintype "passive"))
      (node (ref "U12") (pin "P$18") (pinfunction "COMP_P$18") (pintype "bidirectional"))
    )
    (net (code "112") (name "Net-(U12-FB)") (class "Default")
      (node (ref "R46") (pin "2") (pinfunction "2_2") (pintype "passive"))
      (node (ref "R47") (pin "1") (pinfunction "1_1") (pintype "passive"))
      (node (ref "U12") (pin "P$17") (pinfunction "FB_P$17") (pintype "bidirectional"))
    )
    (net (code "113") (name "Net-(U12-FSW)") (class "Default")
      (node (ref "R43") (pin "1") (pinfunction "1_1") (pintype "passive"))
      (node (ref "U12") (pin "P$3") (pinfunction "FSW_P$3") (pintype "bidirectional"))
    )
    (net (code "114") (name "Net-(U12-ILIM)") (class "Default")
      (node (ref "R44") (pin "2") (pinfunction "2_2") (pintype "passive"))
      (node (ref "U12") (pin "P$19") (pinfunction "ILIM_P$19") (pintype "bidirectional"))
    )
    (net (code "115") (name "Net-(U12-MODE)") (class "Default")
      (node (ref "R48") (pin "1") (pinfunction "1_1") (pintype "passive"))
      (node (ref "U12") (pin "P$13") (pinfunction "MODE_P$13") (pintype "bidirectional"))
    )
    (net (code "116") (name "Net-(U12-SS)") (class "Default")
      (node (ref "C46") (pin "1") (pinfunction "1_1") (pintype "passive"))
      (node (ref "U12") (pin "P$10") (pinfunction "SS_P$10") (pintype "bidirectional"))
    )
    (net (code "117") (name "Net-(U12-VCC)") (class "Default")
      (node (ref "C33") (pin "1") (pinfunction "1_1") (pintype "passive"))
      (node (ref "U12") (pin "P$1") (pinfunction "VCC_P$1") (pintype "bidirectional"))
    )
    (net (code "118") (name "unconnected-(U1-HFXIN-Pad42)") (class "Default")
      (node (ref "U1") (pin "42") (pinfunction "HFXIN_42") (pintype "bidirectional"))
    )
    (net (code "119") (name "unconnected-(U1-HFXOUT-Pad43)") (class "Default")
      (node (ref "U1") (pin "43") (pinfunction "HFXOUT_43") (pintype "bidirectional"))
    )
    (net (code "120") (name "unconnected-(U1-P2.2{slash}TB0.2{slash}UCB0CLK-Pad26)") (class "Default")
      (node (ref "U1") (pin "26") (pinfunction "P2.2/TB0.2/UCB0CLK_26") (pintype "bidirectional"))
    )
    (net (code "121") (name "unconnected-(U1-P2.7-Pad38)") (class "Default")
      (node (ref "U1") (pin "38") (pinfunction "P2.7_38") (pintype "bidirectional"))
    )
    (net (code "122") (name "unconnected-(U1-P3.5{slash}TB0.4-Pad28)") (class "Default")
      (node (ref "U1") (pin "28") (pinfunction "P3.5/TB0.4_28") (pintype "bidirectional"))
    )
    (net (code "123") (name "unconnected-(U1-P3.6{slash}TB0.5-Pad29)") (class "Default")
      (node (ref "U1") (pin "29") (pinfunction "P3.6/TB0.5_29") (pintype "bidirectional"))
    )
    (net (code "124") (name "unconnected-(U1-P3.7{slash}TB0.6-Pad30)") (class "Default")
      (node (ref "U1") (pin "30") (pinfunction "P3.7/TB0.6_30") (pintype "bidirectional"))
    )
    (net (code "125") (name "unconnected-(U1-P4.4{slash}TB0.5-Pad33)") (class "Default")
      (node (ref "U1") (pin "33") (pinfunction "P4.4/TB0.5_33") (pintype "bidirectional"))
    )
    (net (code "126") (name "unconnected-(U1-P4.5-Pad34)") (class "Default")
      (node (ref "U1") (pin "34") (pinfunction "P4.5_34") (pintype "bidirectional"))
    )
    (net (code "127") (name "unconnected-(U1-P4.6-Pad35)") (class "Default")
      (node (ref "U1") (pin "35") (pinfunction "P4.6_35") (pintype "bidirectional"))
    )
    (net (code "128") (name "unconnected-(U1-PJ.3{slash}TCK-Pad15)") (class "Default")
      (node (ref "U1") (pin "15") (pinfunction "PJ.3/TCK_15") (pintype "bidirectional"))
    )
    (net (code "129") (name "unconnected-(U3-OC-Pad5)") (class "Default")
      (node (ref "U3") (pin "5") (pinfunction "OC_5") (pintype "bidirectional"))
    )
    (net (code "130") (name "unconnected-(U7-HYS-Pad8)") (class "Default")
      (node (ref "U7") (pin "8") (pinfunction "HYS_8") (pintype "output"))
    )
  )
)
